# EEZ_CF-DIC_r3B4.net
KiCad netlist of a schematic drawn in EAGLE
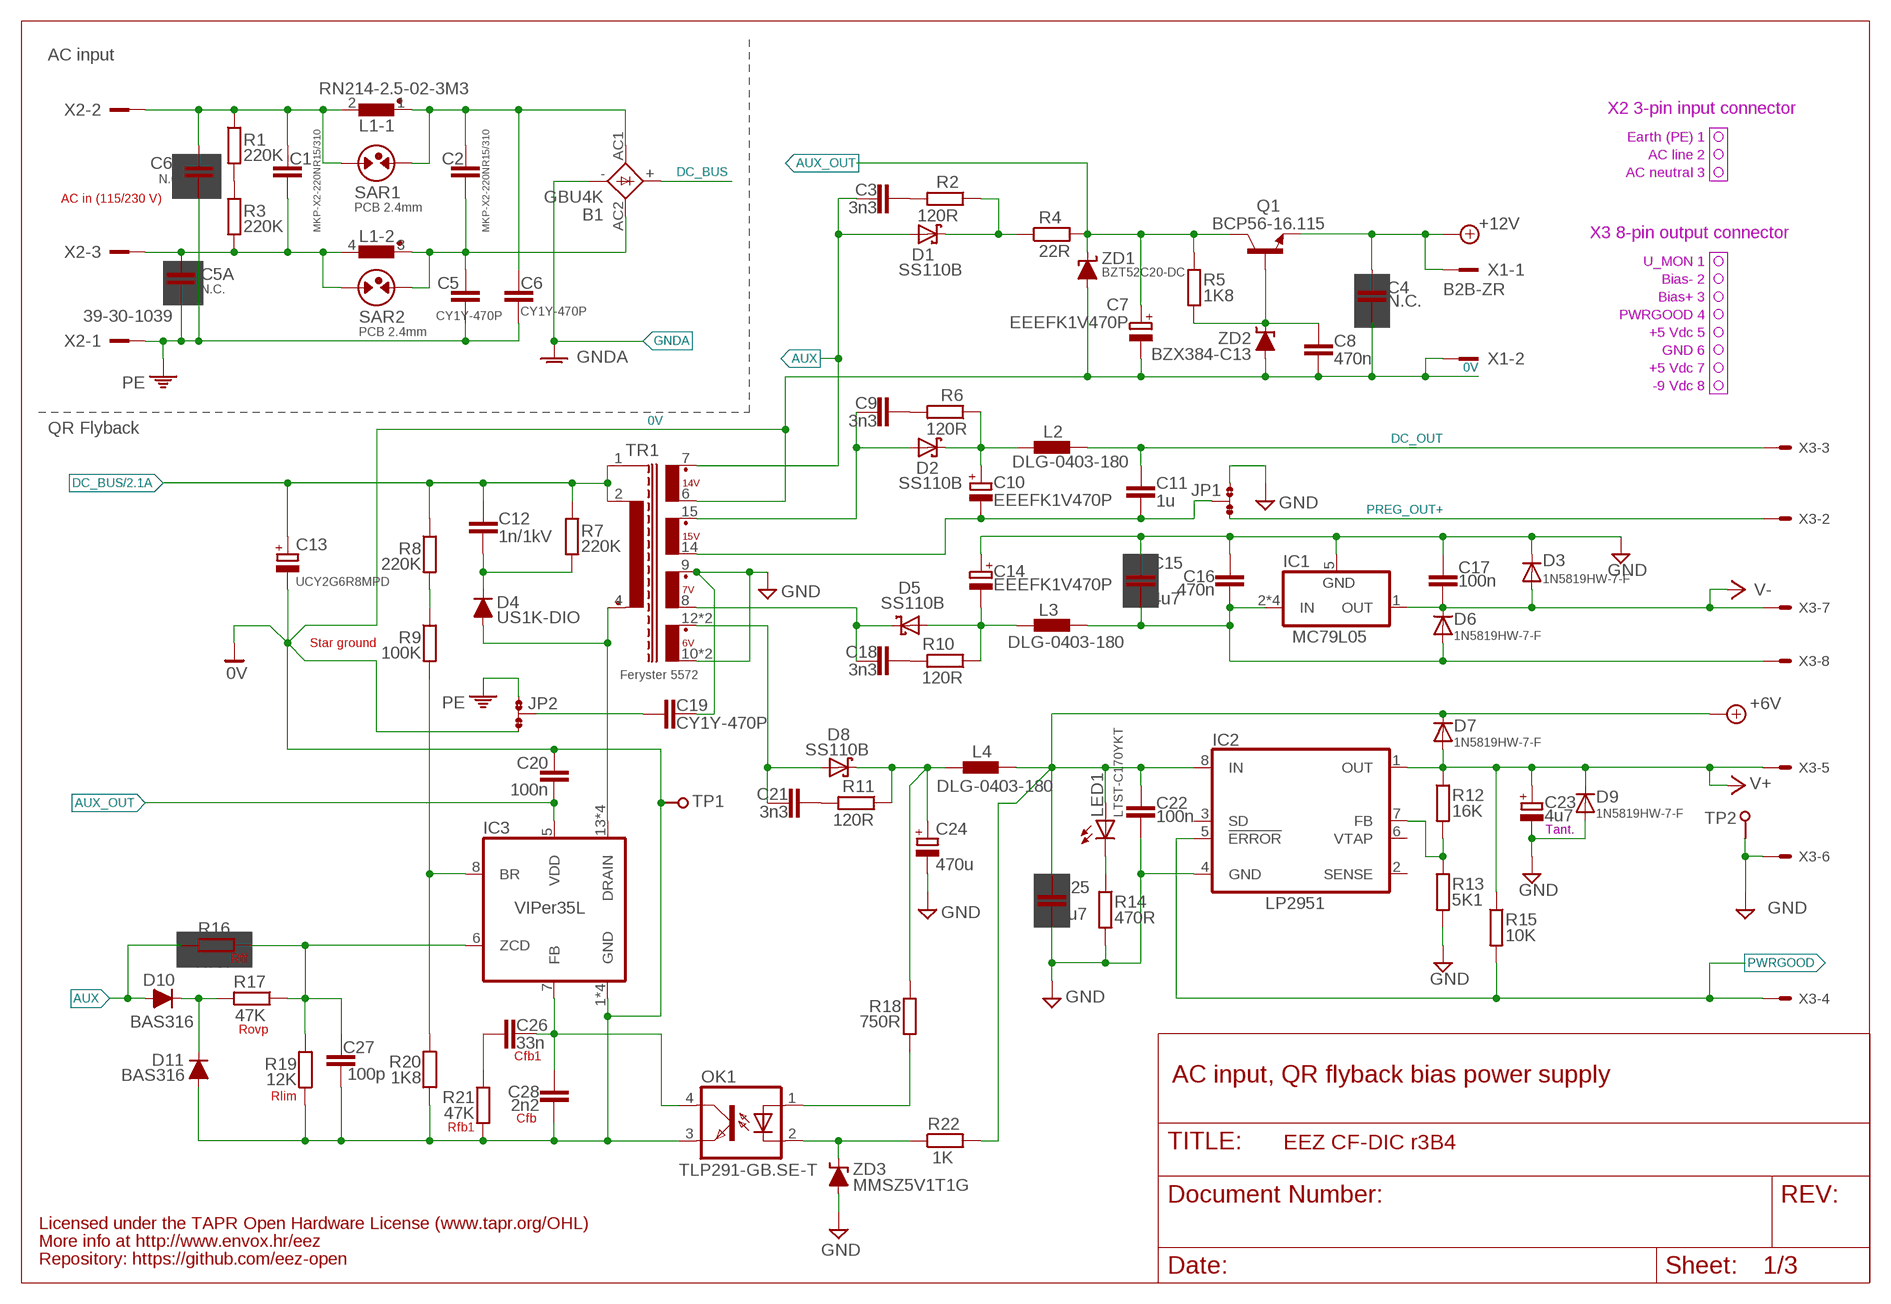
[diagram p0: schematic, sheet 1]
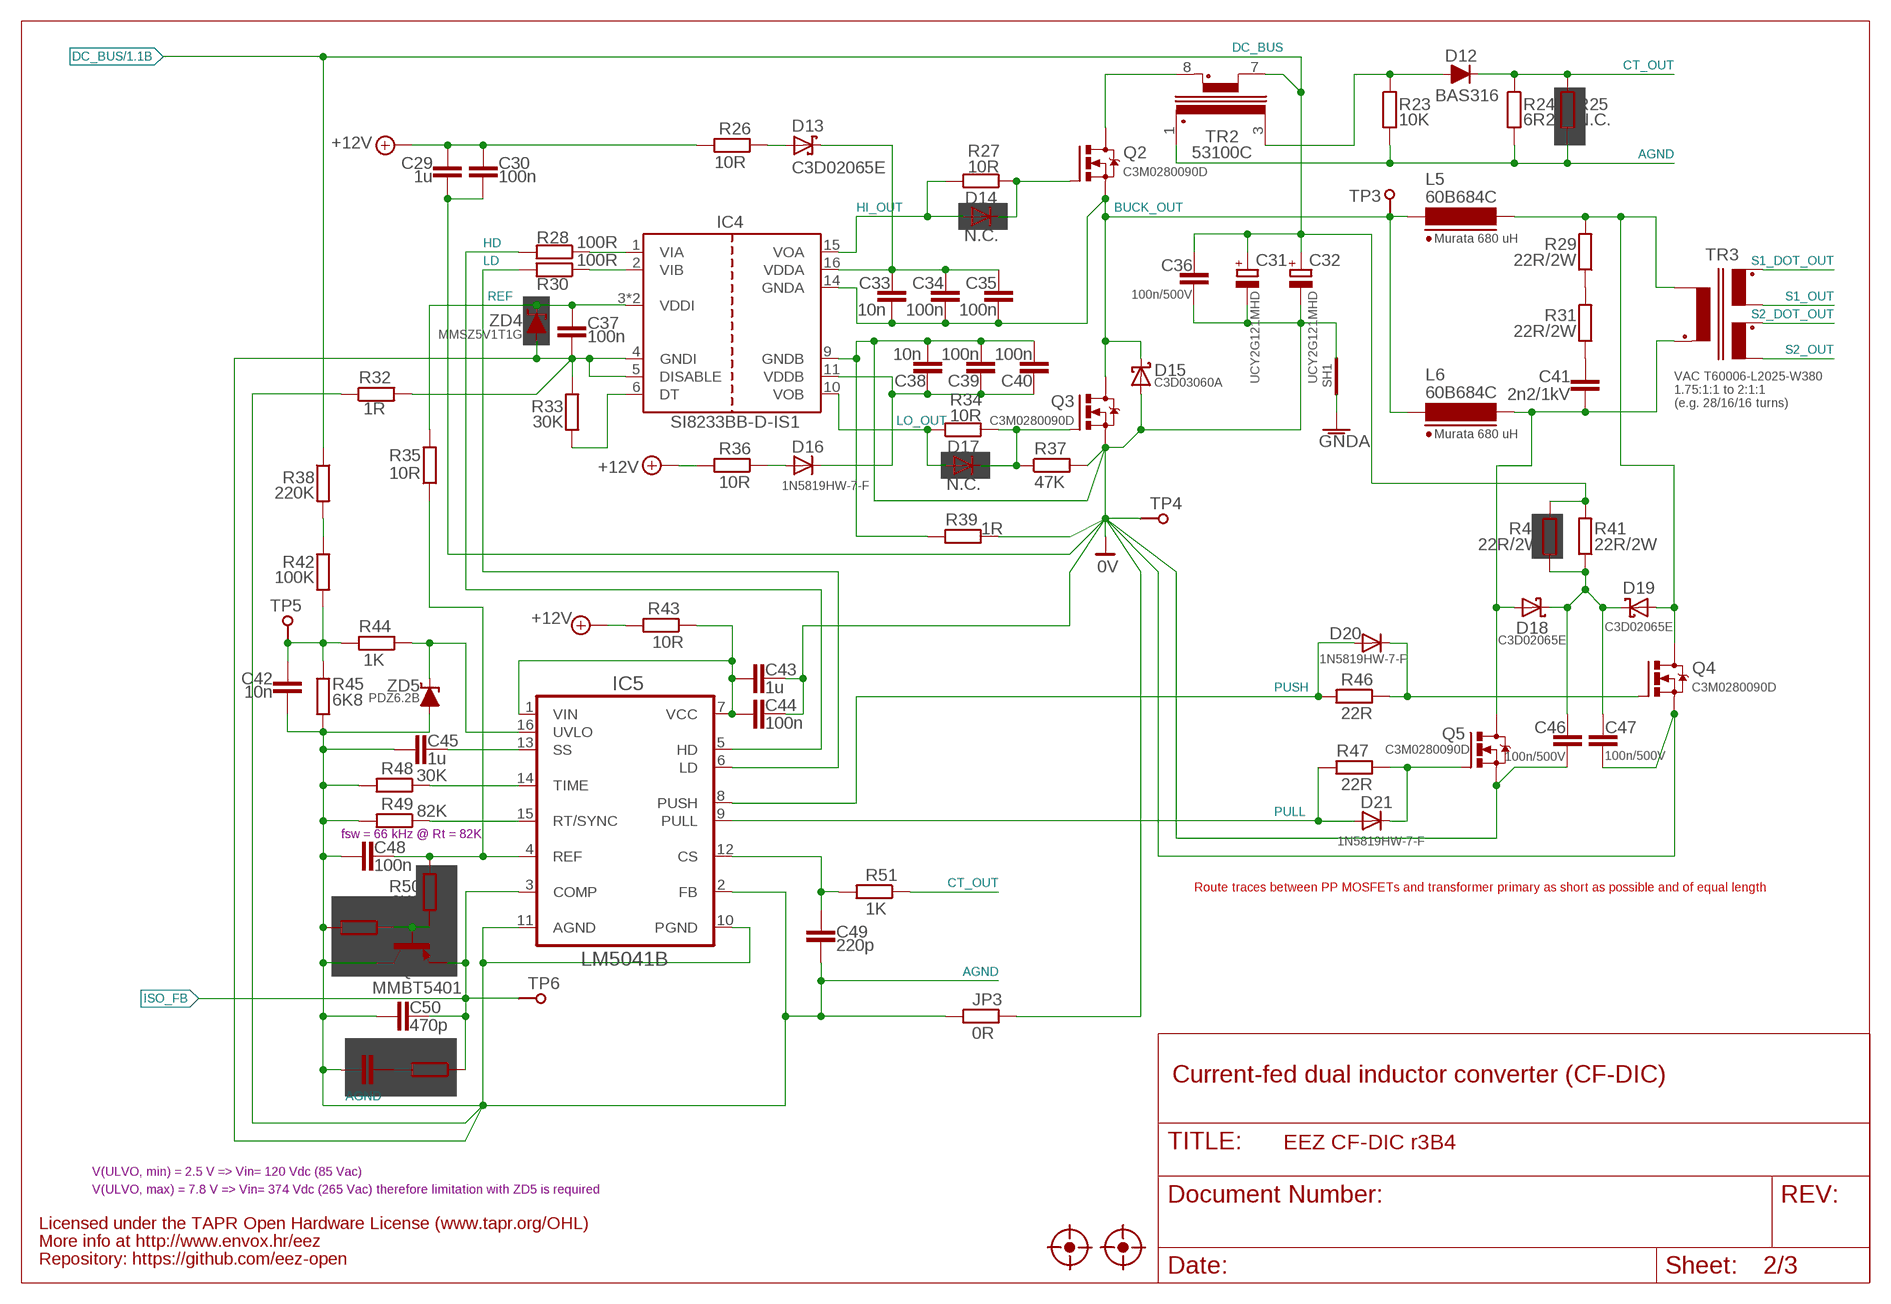
[diagram p1: schematic, sheet 2]
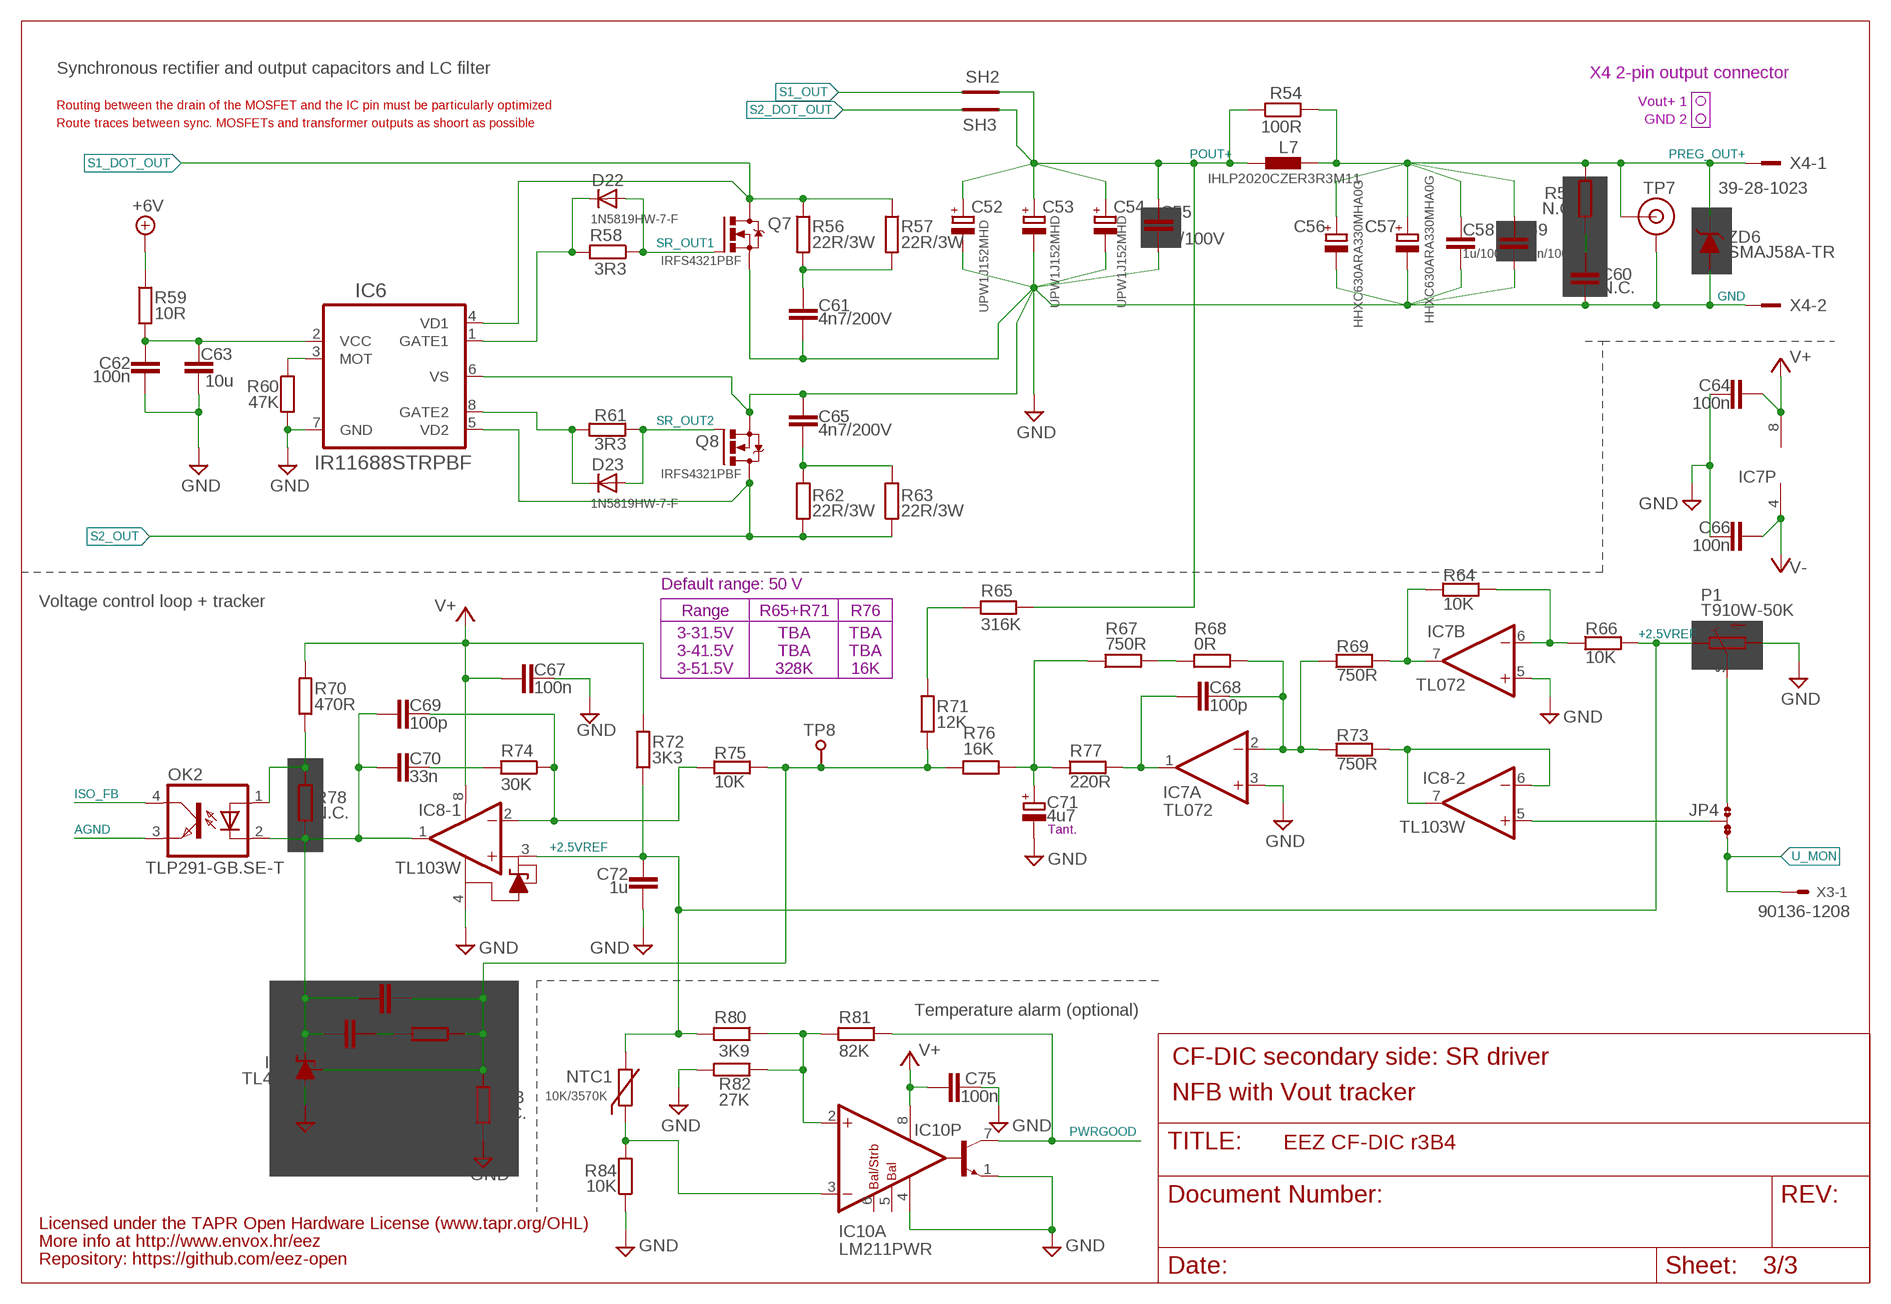
[diagram p2: schematic, sheet 3]

(export (version "E")
  (design (tool "Eeschema 10.0.6"))
  (components
    (comp (ref "B1")
      (value "GBU4K")
      (footprint "eagle-import:GBU4K_CRE")
      (libsource (lib "eagle-import") (part "BRIDGE-CREEPAGE"))
    )
    (comp (ref "C1")
      (value "MKP-X2-220NR15/310")
      (footprint "eagle-import:C150-072X183")
      (libsource (lib "eagle-import") (part "C-EU150-072X183"))
    )
    (comp (ref "C2")
      (value "MKP-X2-220NR15/310")
      (footprint "eagle-import:C150-072X183")
      (libsource (lib "eagle-import") (part "C-EU150-072X183"))
    )
    (comp (ref "C3")
      (value "3n3")
      (footprint "eagle-import:C0805")
      (libsource (lib "eagle-import") (part "C-EUC0805"))
    )
    (comp (ref "C4")
      (value "N.C.")
      (footprint "eagle-import:C0603")
      (libsource (lib "eagle-import") (part "C-EUC0603"))
    )
    (comp (ref "C5")
      (value "CY1Y-470P")
      (footprint "eagle-import:CY075-032X103")
      (libsource (lib "eagle-import") (part "C-EUCY"))
    )
    (comp (ref "C5A")
      (value "N.C.")
      (footprint "eagle-import:CY075-032X103")
      (libsource (lib "eagle-import") (part "C-EUCY"))
    )
    (comp (ref "C6")
      (value "CY1Y-470P")
      (footprint "eagle-import:CY075-032X103")
      (libsource (lib "eagle-import") (part "C-EUCY"))
    )
    (comp (ref "C6A")
      (value "N.C.")
      (footprint "eagle-import:CY075-032X103")
      (libsource (lib "eagle-import") (part "C-EUCY"))
    )
    (comp (ref "C7")
      (value "EEEFK1V470P")
      (footprint "eagle-import:CAPAE660X610N")
      (libsource (lib "eagle-import") (part "ECAPPANASONIC_H"))
    )
    (comp (ref "C8")
      (value "470n")
      (footprint "eagle-import:C0805")
      (libsource (lib "eagle-import") (part "C-EUC0805"))
    )
    (comp (ref "C9")
      (value "3n3")
      (footprint "eagle-import:C0805")
      (libsource (lib "eagle-import") (part "C-EUC0805"))
    )
    (comp (ref "C10")
      (value "EEEFK1V470P")
      (footprint "eagle-import:CAPAE660X610N")
      (libsource (lib "eagle-import") (part "ECAPPANASONIC_H"))
    )
    (comp (ref "C11")
      (value "1u")
      (footprint "eagle-import:C0805")
      (libsource (lib "eagle-import") (part "C-EUC0805"))
    )
    (comp (ref "C12")
      (value "1n/1kV")
      (footprint "eagle-import:C1210")
      (libsource (lib "eagle-import") (part "C-EUC1210"))
    )
    (comp (ref "C13")
      (value "UCY2G6R8MPD")
      (footprint "eagle-import:ECAP5_10.5")
      (libsource (lib "eagle-import") (part "ECAP5G_10.5MM"))
    )
    (comp (ref "C14")
      (value "EEEFK1V470P")
      (footprint "eagle-import:CAPAE660X610N")
      (libsource (lib "eagle-import") (part "ECAPPANASONIC_H"))
    )
    (comp (ref "C15")
      (value "4u7")
      (footprint "eagle-import:C1206")
      (libsource (lib "eagle-import") (part "C-EUC1206"))
    )
    (comp (ref "C16")
      (value "470n")
      (footprint "eagle-import:C0805")
      (libsource (lib "eagle-import") (part "C-EUC0805"))
    )
    (comp (ref "C17")
      (value "100n")
      (footprint "eagle-import:C0603")
      (libsource (lib "eagle-import") (part "C-EUC0603"))
    )
    (comp (ref "C18")
      (value "3n3")
      (footprint "eagle-import:C0805")
      (libsource (lib "eagle-import") (part "C-EUC0805"))
    )
    (comp (ref "C19")
      (value "CY1Y-470P")
      (footprint "eagle-import:CY075-032X103")
      (libsource (lib "eagle-import") (part "C-EUCY"))
    )
    (comp (ref "C20")
      (value "100n")
      (footprint "eagle-import:C0603")
      (libsource (lib "eagle-import") (part "C-EUC0603"))
    )
    (comp (ref "C21")
      (value "3n3")
      (footprint "eagle-import:C0805")
      (libsource (lib "eagle-import") (part "C-EUC0805"))
    )
    (comp (ref "C22")
      (value "100n")
      (footprint "eagle-import:C0603")
      (libsource (lib "eagle-import") (part "C-EUC0603"))
    )
    (comp (ref "C23")
      (value "4u7")
      (footprint "eagle-import:EC1206")
      (libsource (lib "eagle-import") (part "ECAP1206"))
    )
    (comp (ref "C24")
      (value "470u")
      (footprint "eagle-import:ECAP5_10.5")
      (libsource (lib "eagle-import") (part "ECAP5G_10.5MM"))
    )
    (comp (ref "C25")
      (value "4u7")
      (footprint "eagle-import:C1206")
      (libsource (lib "eagle-import") (part "C-EUC1206"))
    )
    (comp (ref "C26")
      (value "33n")
      (footprint "eagle-import:C0805")
      (libsource (lib "eagle-import") (part "C-EUC0805"))
    )
    (comp (ref "C27")
      (value "100p")
      (footprint "eagle-import:C0805")
      (libsource (lib "eagle-import") (part "C-EUC0805"))
    )
    (comp (ref "C28")
      (value "2n2")
      (footprint "eagle-import:C0805")
      (libsource (lib "eagle-import") (part "C-EUC0805"))
    )
    (comp (ref "D1")
      (value "SS110B")
      (footprint "eagle-import:SMB")
      (libsource (lib "eagle-import") (part "SCHOTTKYSMB"))
    )
    (comp (ref "D2")
      (value "SS110B")
      (footprint "eagle-import:SMB")
      (libsource (lib "eagle-import") (part "SCHOTTKYSMB"))
    )
    (comp (ref "D3")
      (value "1N5819HW-7-F")
      (footprint "eagle-import:SOD323-W")
      (libsource (lib "eagle-import") (part "DIODE-SOD323-W"))
    )
    (comp (ref "D4")
      (value "US1K-DIO")
      (footprint "eagle-import:DO214AA")
      (libsource (lib "eagle-import") (part "DIODEDO214AA"))
    )
    (comp (ref "D5")
      (value "SS110B")
      (footprint "eagle-import:SMB")
      (libsource (lib "eagle-import") (part "SCHOTTKYSMB"))
    )
    (comp (ref "D6")
      (value "1N5819HW-7-F")
      (footprint "eagle-import:SOD323-W")
      (libsource (lib "eagle-import") (part "DIODE-SOD323-W"))
    )
    (comp (ref "D7")
      (value "1N5819HW-7-F")
      (footprint "eagle-import:SOD323-W")
      (libsource (lib "eagle-import") (part "DIODE-SOD323-W"))
    )
    (comp (ref "D8")
      (value "SS110B")
      (footprint "eagle-import:SMB")
      (libsource (lib "eagle-import") (part "SCHOTTKYSMB"))
    )
    (comp (ref "D9")
      (value "1N5819HW-7-F")
      (footprint "eagle-import:SOD323-W")
      (libsource (lib "eagle-import") (part "DIODE-SOD323-W"))
    )
    (comp (ref "D10")
      (value "BAS316")
      (footprint "eagle-import:SOD323-R")
      (libsource (lib "eagle-import") (part "DIODESOD323R"))
    )
    (comp (ref "D11")
      (value "BAS316")
      (footprint "eagle-import:SOD323-R")
      (libsource (lib "eagle-import") (part "DIODESOD323R"))
    )
    (comp (ref "IC1")
      (value "MC79L05")
      (footprint "eagle-import:SOIC127P600X173-8N")
      (libsource (lib "eagle-import") (part "MC79LXXSOIC"))
    )
    (comp (ref "IC2")
      (value "LP2951")
      (footprint "eagle-import:SOIC127P600X175-8N")
      (libsource (lib "eagle-import") (part "LP2951SO8"))
    )
    (comp (ref "IC3")
      (value "VIPer35L")
      (footprint "eagle-import:SOIC-16")
      (libsource (lib "eagle-import") (part "VIPER35"))
    )
    (comp (ref "JP1")
      (value "JP3-CUT")
      (footprint "eagle-import:JP3-CUT")
      (libsource (lib "eagle-import") (part "JP3-CUT"))
    )
    (comp (ref "JP2")
      (value "JP3-CUT")
      (footprint "eagle-import:JP3-CUT")
      (libsource (lib "eagle-import") (part "JP3-CUT"))
    )
    (comp (ref "L1")
      (value "RN214-2.5-02-3M3")
      (footprint "eagle-import:RN214")
      (fields (field (name "FARNELL") "1191518"))
      (libsource (lib "eagle-import") (part "EEZ_inductors_and_transformers_RN214"))
    )
    (comp (ref "L2")
      (value "DLG-0403-180")
      (footprint "eagle-import:DE0403")
      (libsource (lib "eagle-import") (part "EEZ_inductors_and_transformers_DE0403"))
    )
    (comp (ref "L3")
      (value "DLG-0403-180")
      (footprint "eagle-import:DE0403")
      (libsource (lib "eagle-import") (part "EEZ_inductors_and_transformers_DE0403"))
    )
    (comp (ref "L4")
      (value "DLG-0403-180")
      (footprint "eagle-import:DE0403")
      (libsource (lib "eagle-import") (part "EEZ_inductors_and_transformers_DE0403"))
    )
    (comp (ref "LED1")
      (value "LTST-C170YKT")
      (footprint "eagle-import:LED_0805")
      (libsource (lib "eagle-import") (part "LED0805"))
    )
    (comp (ref "OK1")
      (value "TLP291-GB.SE-T")
      (footprint "eagle-import:SO4")
      (libsource (lib "eagle-import") (part "TLP291"))
    )
    (comp (ref "Q1")
      (value "BCP56-16.115")
      (footprint "eagle-import:SOT230P700X180-4N")
      (libsource (lib "eagle-import") (part "BCP56"))
    )
    (comp (ref "R1")
      (value "220K")
      (footprint "eagle-import:R1206")
      (libsource (lib "eagle-import") (part "R-EU_R1206"))
    )
    (comp (ref "R2")
      (value "120R")
      (footprint "eagle-import:R0805")
      (libsource (lib "eagle-import") (part "R-EU_R0805"))
    )
    (comp (ref "R3")
      (value "220K")
      (footprint "eagle-import:R1206")
      (libsource (lib "eagle-import") (part "R-EU_R1206"))
    )
    (comp (ref "R4")
      (value "22R")
      (footprint "eagle-import:R0805")
      (libsource (lib "eagle-import") (part "R-EU_R0805"))
    )
    (comp (ref "R5")
      (value "1K8")
      (footprint "eagle-import:R0805")
      (libsource (lib "eagle-import") (part "R-EU_R0805"))
    )
    (comp (ref "R6")
      (value "120R")
      (footprint "eagle-import:R0805")
      (libsource (lib "eagle-import") (part "R-EU_R0805"))
    )
    (comp (ref "R7")
      (value "220K")
      (footprint "eagle-import:R1206")
      (libsource (lib "eagle-import") (part "R-EU_R1206"))
    )
    (comp (ref "R8")
      (value "220K")
      (footprint "eagle-import:R1206")
      (libsource (lib "eagle-import") (part "R-EU_R1206"))
    )
    (comp (ref "R9")
      (value "100K")
      (footprint "eagle-import:R0805")
      (libsource (lib "eagle-import") (part "R-EU_R0805"))
    )
    (comp (ref "R10")
      (value "120R")
      (footprint "eagle-import:R0805")
      (libsource (lib "eagle-import") (part "R-EU_R0805"))
    )
    (comp (ref "R11")
      (value "120R")
      (footprint "eagle-import:R0805")
      (libsource (lib "eagle-import") (part "R-EU_R0805"))
    )
    (comp (ref "R12")
      (value "16K")
      (footprint "eagle-import:R0805")
      (libsource (lib "eagle-import") (part "R-EU_R0805"))
    )
    (comp (ref "R13")
      (value "5K1")
      (footprint "eagle-import:R0805")
      (libsource (lib "eagle-import") (part "R-EU_R0805"))
    )
    (comp (ref "R14")
      (value "470R")
      (footprint "eagle-import:R0805")
      (libsource (lib "eagle-import") (part "R-EU_R0805"))
    )
    (comp (ref "R15")
      (value "10K")
      (footprint "eagle-import:R0805")
      (libsource (lib "eagle-import") (part "R-EU_R0805"))
    )
    (comp (ref "R16")
      (value "N.C.")
      (footprint "eagle-import:R0805")
      (libsource (lib "eagle-import") (part "R-EU_R0805"))
    )
    (comp (ref "R17")
      (value "47K")
      (footprint "eagle-import:R0805")
      (libsource (lib "eagle-import") (part "R-EU_R0805"))
    )
    (comp (ref "R18")
      (value "750R")
      (footprint "eagle-import:R0805")
      (libsource (lib "eagle-import") (part "R-EU_R0805"))
    )
    (comp (ref "R19")
      (value "12K")
      (footprint "eagle-import:R0805")
      (libsource (lib "eagle-import") (part "R-EU_R0805"))
    )
    (comp (ref "R20")
      (value "1K8")
      (footprint "eagle-import:R0805")
      (libsource (lib "eagle-import") (part "R-EU_R0805"))
    )
    (comp (ref "R21")
      (value "47K")
      (footprint "eagle-import:R0805")
      (libsource (lib "eagle-import") (part "R-EU_R0805"))
    )
    (comp (ref "R22")
      (value "1K")
      (footprint "eagle-import:R0805")
      (libsource (lib "eagle-import") (part "R-EU_R0805"))
    )
    (comp (ref "SAR1")
      (value "PCB 2.4mm")
      (footprint "eagle-import:PCB-SAR_2.4MM")
      (libsource (lib "eagle-import") (part "SARPCB-2.4MM"))
    )
    (comp (ref "SAR2")
      (value "PCB 2.4mm")
      (footprint "eagle-import:PCB-SAR_2.4MM")
      (libsource (lib "eagle-import") (part "SARPCB-2.4MM"))
    )
    (comp (ref "TP1")
      (value "PCB_TEST_TABSHIELD")
      (footprint "eagle-import:PCB_SHIELD_TAB")
      (libsource (lib "eagle-import") (part "PCB_TEST_TABSHIELD"))
    )
    (comp (ref "TP2")
      (value "PCB_TEST_TABSHIELD")
      (footprint "eagle-import:PCB_SHIELD_TAB")
      (libsource (lib "eagle-import") (part "PCB_TEST_TABSHIELD"))
    )
    (comp (ref "TR1")
      (value "Feryster 5572")
      (footprint "eagle-import:FERYSTER_5572")
      (libsource (lib "eagle-import") (part "EEZ_inductors_and_transformers_FERYSTER_5572"))
    )
    (comp (ref "X1")
      (value "B2B-ZR")
      (footprint "eagle-import:B2B-ZR")
      (libsource (lib "eagle-import") (part "B2B-ZR"))
    )
    (comp (ref "X2")
      (value "39-30-1039")
      (footprint "eagle-import:MINIFIT_39301039_CRE")
      (libsource (lib "eagle-import") (part "MINIFIT_39301039-CREEPAGE"))
    )
    (comp (ref "X3")
      (value "90136-1208")
      (footprint "eagle-import:70543-08")
      (libsource (lib "eagle-import") (part "C-GRID-08-70543"))
    )
    (comp (ref "ZD1")
      (value "BZT52C20-DC")
      (footprint "eagle-import:SOD123FL")
      (libsource (lib "eagle-import") (part "ZENER-DIODESOD123FL"))
    )
    (comp (ref "ZD2")
      (value "BZX384-C13")
      (footprint "eagle-import:SOD323-W")
      (libsource (lib "eagle-import") (part "ZENER-DIODESOD323"))
    )
    (comp (ref "ZD3")
      (value "MMSZ5V1T1G")
      (footprint "eagle-import:SOD323-W")
      (libsource (lib "eagle-import") (part "ZENER-DIODESOD323"))
    )
    (comp (ref "C29")
      (value "1u")
      (footprint "eagle-import:C0805")
      (libsource (lib "eagle-import") (part "C-EUC0805"))
    )
    (comp (ref "C30")
      (value "100n")
      (footprint "eagle-import:C0603")
      (libsource (lib "eagle-import") (part "C-EUC0603"))
    )
    (comp (ref "C31")
      (value "UCY2G121MHD")
      (footprint "eagle-import:ECAP7.5_18")
      (libsource (lib "eagle-import") (part "ECAP7.5G_18MM"))
    )
    (comp (ref "C32")
      (value "UCY2G121MHD")
      (footprint "eagle-import:ECAP7.5_18")
      (libsource (lib "eagle-import") (part "ECAP7.5G_18MM"))
    )
    (comp (ref "C33")
      (value "10n")
      (footprint "eagle-import:C0603")
      (libsource (lib "eagle-import") (part "C-EUC0603"))
    )
    (comp (ref "C34")
      (value "100n")
      (footprint "eagle-import:C0603")
      (libsource (lib "eagle-import") (part "C-EUC0603"))
    )
    (comp (ref "C35")
      (value "100n")
      (footprint "eagle-import:C0603")
      (libsource (lib "eagle-import") (part "C-EUC0603"))
    )
    (comp (ref "C36")
      (value "100n/500V")
      (footprint "eagle-import:C1812")
      (libsource (lib "eagle-import") (part "C-EUC1812"))
    )
    (comp (ref "C37")
      (value "100n")
      (footprint "eagle-import:C0603")
      (libsource (lib "eagle-import") (part "C-EUC0603"))
    )
    (comp (ref "C38")
      (value "10n")
      (footprint "eagle-import:C0603")
      (libsource (lib "eagle-import") (part "C-EUC0603"))
    )
    (comp (ref "C39")
      (value "100n")
      (footprint "eagle-import:C0603")
      (libsource (lib "eagle-import") (part "C-EUC0603"))
    )
    (comp (ref "C40")
      (value "100n")
      (footprint "eagle-import:C0603")
      (libsource (lib "eagle-import") (part "C-EUC0603"))
    )
    (comp (ref "C41")
      (value "2n2/1kV")
      (footprint "eagle-import:C1210")
      (libsource (lib "eagle-import") (part "C-EUC1210"))
    )
    (comp (ref "C42")
      (value "10n")
      (footprint "eagle-import:C0603")
      (libsource (lib "eagle-import") (part "C-EUC0603"))
    )
    (comp (ref "C43")
      (value "1u")
      (footprint "eagle-import:C0805")
      (libsource (lib "eagle-import") (part "C-EUC0805"))
    )
    (comp (ref "C44")
      (value "100n")
      (footprint "eagle-import:C0603")
      (libsource (lib "eagle-import") (part "C-EUC0603"))
    )
    (comp (ref "C45")
      (value "1u")
      (footprint "eagle-import:C0805")
      (libsource (lib "eagle-import") (part "C-EUC0805"))
    )
    (comp (ref "C46")
      (value "100n/500V")
      (footprint "eagle-import:C1812")
      (libsource (lib "eagle-import") (part "C-EUC1812"))
    )
    (comp (ref "C47")
      (value "100n/500V")
      (footprint "eagle-import:C1812")
      (libsource (lib "eagle-import") (part "C-EUC1812"))
    )
    (comp (ref "C48")
      (value "100n")
      (footprint "eagle-import:C0603")
      (libsource (lib "eagle-import") (part "C-EUC0603"))
    )
    (comp (ref "C49")
      (value "220p")
      (footprint "eagle-import:C0805")
      (libsource (lib "eagle-import") (part "C-EUC0805"))
    )
    (comp (ref "C50")
      (value "470p")
      (footprint "eagle-import:C0805")
      (libsource (lib "eagle-import") (part "C-EUC0805"))
    )
    (comp (ref "C51")
      (value "N.C.")
      (footprint "eagle-import:C0805")
      (libsource (lib "eagle-import") (part "C-EUC0805"))
    )
    (comp (ref "D12")
      (value "BAS316")
      (footprint "eagle-import:SOD323-R")
      (libsource (lib "eagle-import") (part "DIODESOD323R"))
    )
    (comp (ref "D13")
      (value "C3D02065E")
      (footprint "eagle-import:TO252")
      (libsource (lib "eagle-import") (part "SCHOTTKY-2"))
    )
    (comp (ref "D14")
      (value "N.C.")
      (footprint "eagle-import:SOD323-W")
      (libsource (lib "eagle-import") (part "DIODE-SOD323-W"))
    )
    (comp (ref "D15")
      (value "C3D03060A")
      (footprint "eagle-import:TO220-2")
      (libsource (lib "eagle-import") (part "SCHOTTKY-TO220"))
    )
    (comp (ref "D16")
      (value "1N5819HW-7-F")
      (footprint "eagle-import:SOD323-W")
      (libsource (lib "eagle-import") (part "DIODE-SOD323-W"))
    )
    (comp (ref "D17")
      (value "N.C.")
      (footprint "eagle-import:SOD323-W")
      (libsource (lib "eagle-import") (part "DIODE-SOD323-W"))
    )
    (comp (ref "D18")
      (value "C3D02065E")
      (footprint "eagle-import:TO252")
      (libsource (lib "eagle-import") (part "SCHOTTKY-2"))
    )
    (comp (ref "D19")
      (value "C3D02065E")
      (footprint "eagle-import:TO252")
      (libsource (lib "eagle-import") (part "SCHOTTKY-2"))
    )
    (comp (ref "D20")
      (value "1N5819HW-7-F")
      (footprint "eagle-import:SOD323-W")
      (libsource (lib "eagle-import") (part "DIODE-SOD323-W"))
    )
    (comp (ref "D21")
      (value "1N5819HW-7-F")
      (footprint "eagle-import:SOD323-W")
      (libsource (lib "eagle-import") (part "DIODE-SOD323-W"))
    )
    (comp (ref "FM1")
      (value "FIDUCIAL_2")
      (footprint "eagle-import:FIDUCIAL_DUAL")
      (libsource (lib "eagle-import") (part "FIDUCIAL_2"))
    )
    (comp (ref "FM2")
      (value "FIDUCIAL_2")
      (footprint "eagle-import:FIDUCIAL_DUAL")
      (libsource (lib "eagle-import") (part "FIDUCIAL_2"))
    )
    (comp (ref "IC4")
      (value "SI8233BB-D-IS1")
      (footprint "eagle-import:SOIC-16")
      (libsource (lib "eagle-import") (part "SI8233"))
    )
    (comp (ref "IC5")
      (value "LM5041B")
      (footprint "eagle-import:MTC16")
      (fields (field (name "MANUFACTURER_PART_NUMBER") "lm5041mtcnopb"))
      (libsource (lib "eagle-import") (part "LM5041"))
    )
    (comp (ref "JP3")
      (value "0R")
      (footprint "eagle-import:R0805")
      (libsource (lib "eagle-import") (part "R-EU_R0805"))
    )
    (comp (ref "L5")
      (value "60B684C")
      (footprint "eagle-import:MURATA_6000B")
      (libsource (lib "eagle-import") (part "EEZ_inductors_and_transformers_MURATA_6000B"))
    )
    (comp (ref "L6")
      (value "60B684C")
      (footprint "eagle-import:MURATA_6000B")
      (libsource (lib "eagle-import") (part "EEZ_inductors_and_transformers_MURATA_6000B"))
    )
    (comp (ref "Q2")
      (value "C3M0280090D")
      (footprint "eagle-import:TO247BV")
      (libsource (lib "eagle-import") (part "IRFP240"))
    )
    (comp (ref "Q3")
      (value "C3M0280090D")
      (footprint "eagle-import:TO247BV")
      (libsource (lib "eagle-import") (part "IRFP240"))
    )
    (comp (ref "Q4")
      (value "C3M0280090D")
      (footprint "eagle-import:TO247BV")
      (libsource (lib "eagle-import") (part "IRFP240"))
    )
    (comp (ref "Q5")
      (value "C3M0280090D")
      (footprint "eagle-import:TO247BV")
      (libsource (lib "eagle-import") (part "IRFP240"))
    )
    (comp (ref "Q6")
      (value "MMBT5401")
      (footprint "eagle-import:SOT23-BEC")
      (libsource (lib "eagle-import") (part "-PNP-SOT23-BECBC857B"))
    )
    (comp (ref "R23")
      (value "10K")
      (footprint "eagle-import:R0805")
      (libsource (lib "eagle-import") (part "R-EU_R0805"))
    )
    (comp (ref "R24")
      (value "6R2")
      (footprint "eagle-import:R0805")
      (libsource (lib "eagle-import") (part "R-EU_R0805"))
    )
    (comp (ref "R25")
      (value "N.C.")
      (footprint "eagle-import:R0805")
      (libsource (lib "eagle-import") (part "R-EU_R0805"))
    )
    (comp (ref "R26")
      (value "10R")
      (footprint "eagle-import:R0805")
      (libsource (lib "eagle-import") (part "R-EU_R0805"))
    )
    (comp (ref "R27")
      (value "10R")
      (footprint "eagle-import:R0805")
      (libsource (lib "eagle-import") (part "R-EU_R0805"))
    )
    (comp (ref "R28")
      (value "100R")
      (footprint "eagle-import:R0805")
      (libsource (lib "eagle-import") (part "R-EU_R0805"))
    )
    (comp (ref "R29")
      (value "22R/2W")
      (footprint "eagle-import:R2512")
      (libsource (lib "eagle-import") (part "R-EU_R2512"))
    )
    (comp (ref "R30")
      (value "100R")
      (footprint "eagle-import:R0805")
      (libsource (lib "eagle-import") (part "R-EU_R0805"))
    )
    (comp (ref "R31")
      (value "22R/2W")
      (footprint "eagle-import:R2512")
      (libsource (lib "eagle-import") (part "R-EU_R2512"))
    )
    (comp (ref "R32")
      (value "1R")
      (footprint "eagle-import:R0805")
      (libsource (lib "eagle-import") (part "R-EU_R0805"))
    )
    (comp (ref "R33")
      (value "30K")
      (footprint "eagle-import:R0805")
      (libsource (lib "eagle-import") (part "R-EU_R0805"))
    )
    (comp (ref "R34")
      (value "10R")
      (footprint "eagle-import:R0805")
      (libsource (lib "eagle-import") (part "R-EU_R0805"))
    )
    (comp (ref "R35")
      (value "10R")
      (footprint "eagle-import:R0805")
      (libsource (lib "eagle-import") (part "R-EU_R0805"))
    )
    (comp (ref "R36")
      (value "10R")
      (footprint "eagle-import:R0805")
      (libsource (lib "eagle-import") (part "R-EU_R0805"))
    )
    (comp (ref "R37")
      (value "47K")
      (footprint "eagle-import:R0805")
      (libsource (lib "eagle-import") (part "R-EU_R0805"))
    )
    (comp (ref "R38")
      (value "220K")
      (footprint "eagle-import:R1206")
      (libsource (lib "eagle-import") (part "R-EU_R1206"))
    )
    (comp (ref "R39")
      (value "1R")
      (footprint "eagle-import:R0805")
      (libsource (lib "eagle-import") (part "R-EU_R0805"))
    )
    (comp (ref "R40")
      (value "22R/2W")
      (footprint "eagle-import:R2512")
      (libsource (lib "eagle-import") (part "R-EU_R2512"))
    )
    (comp (ref "R41")
      (value "22R/2W")
      (footprint "eagle-import:R2512")
      (libsource (lib "eagle-import") (part "R-EU_R2512"))
    )
    (comp (ref "R42")
      (value "100K")
      (footprint "eagle-import:R0805")
      (libsource (lib "eagle-import") (part "R-EU_R0805"))
    )
    (comp (ref "R43")
      (value "10R")
      (footprint "eagle-import:R0805")
      (libsource (lib "eagle-import") (part "R-EU_R0805"))
    )
    (comp (ref "R44")
      (value "1K")
      (footprint "eagle-import:R0805")
      (libsource (lib "eagle-import") (part "R-EU_R0805"))
    )
    (comp (ref "R45")
      (value "6K8")
      (footprint "eagle-import:R0805")
      (libsource (lib "eagle-import") (part "R-EU_R0805"))
    )
    (comp (ref "R46")
      (value "22R")
      (footprint "eagle-import:R0805")
      (libsource (lib "eagle-import") (part "R-EU_R0805"))
    )
    (comp (ref "R47")
      (value "22R")
      (footprint "eagle-import:R0805")
      (libsource (lib "eagle-import") (part "R-EU_R0805"))
    )
    (comp (ref "R48")
      (value "30K")
      (footprint "eagle-import:R0805")
      (libsource (lib "eagle-import") (part "R-EU_R0805"))
    )
    (comp (ref "R49")
      (value "82K")
      (footprint "eagle-import:R0805")
      (libsource (lib "eagle-import") (part "R-EU_R0805"))
    )
    (comp (ref "R50")
      (value "6K8")
      (footprint "eagle-import:R0805")
      (libsource (lib "eagle-import") (part "R-EU_R0805"))
    )
    (comp (ref "R51")
      (value "1K")
      (footprint "eagle-import:R0805")
      (libsource (lib "eagle-import") (part "R-EU_R0805"))
    )
    (comp (ref "R52")
      (value "6K8")
      (footprint "eagle-import:R0805")
      (libsource (lib "eagle-import") (part "R-EU_R0805"))
    )
    (comp (ref "R53")
      (value "N.C.")
      (footprint "eagle-import:R0805")
      (libsource (lib "eagle-import") (part "R-EU_R0805"))
    )
    (comp (ref "SH1")
      (value "SHORTNOHOLE")
      (footprint "eagle-import:SHORT_NOHOLE")
      (libsource (lib "eagle-import") (part "SHORTNOHOLE"))
    )
    (comp (ref "TP3")
      (value "PCB_TEST_TABSHIELD")
      (footprint "eagle-import:PCB_SHIELD_TAB")
      (libsource (lib "eagle-import") (part "PCB_TEST_TABSHIELD"))
    )
    (comp (ref "TP4")
      (value "PCB_TEST_TABSHIELD")
      (footprint "eagle-import:PCB_SHIELD_TAB")
      (libsource (lib "eagle-import") (part "PCB_TEST_TABSHIELD"))
    )
    (comp (ref "TP5")
      (value "PCB_TEST_TABSHIELD")
      (footprint "eagle-import:PCB_SHIELD_TAB")
      (libsource (lib "eagle-import") (part "PCB_TEST_TABSHIELD"))
    )
    (comp (ref "TP6")
      (value "PCB_TEST_TABSHIELD")
      (footprint "eagle-import:PCB_SHIELD_TAB")
      (libsource (lib "eagle-import") (part "PCB_TEST_TABSHIELD"))
    )
    (comp (ref "TR2")
      (value "53100C")
      (footprint "eagle-import:MURATA_5300")
      (libsource (lib "eagle-import") (part "MURATA_5300"))
    )
    (comp (ref "TR3")
      (value "VAC T60006-L2025-W380")
      (footprint "eagle-import:VAC_DUAL_SEC")
      (libsource (lib "eagle-import") (part "PCB_TRAFO_FLYBACK2-VAC"))
    )
    (comp (ref "ZD4")
      (value "MMSZ5V1T1G")
      (footprint "eagle-import:SOD323-W")
      (libsource (lib "eagle-import") (part "ZENER-DIODESOD323"))
    )
    (comp (ref "ZD5")
      (value "PDZ6.2B")
      (footprint "eagle-import:SOD323-W")
      (libsource (lib "eagle-import") (part "ZENER-DIODESOD323"))
    )
    (comp (ref "C52")
      (value "UPW1J152MHD")
      (footprint "eagle-import:ECAP7.5_18")
      (libsource (lib "eagle-import") (part "ECAP7.5G_18MM"))
    )
    (comp (ref "C53")
      (value "UPW1J152MHD")
      (footprint "eagle-import:ECAP7.5_18")
      (libsource (lib "eagle-import") (part "ECAP7.5G_18MM"))
    )
    (comp (ref "C54")
      (value "UPW1J152MHD")
      (footprint "eagle-import:ECAP7.5_18")
      (libsource (lib "eagle-import") (part "ECAP7.5G_18MM"))
    )
    (comp (ref "C55")
      (value "1u/100V")
      (footprint "eagle-import:C1206")
      (libsource (lib "eagle-import") (part "C-EUC1206"))
    )
    (comp (ref "C56")
      (value "HHXC630ARA330MHA0G ")
      (footprint "eagle-import:CAPAE830X1050N")
      (fields
        (field (name "MPN") "EEE-FK1J470P")
        (field (name "TOLERANCE") "±20 %")
        (field (name "MPN_1") "EEE-FK1J470P")
        (field (name "OC_FARNELL") "9696032  ")
        (field (name "OC_NEWARK") "96K9403")
        (field (name "PACKAGE") "CASE-F")
        (field (name "SUPPLIER") "PANASONIC")
        (field (name "TOLERANCE_1") "±20 %")
        (field (name "VOLTAGERATING") "63 V")
      )
      (libsource (lib "eagle-import") (part "EEE--CASE-FFK1J470P"))
    )
    (comp (ref "C57")
      (value "HHXC630ARA330MHA0G")
      (footprint "eagle-import:CAPAE830X1050N")
      (fields (field (name "MPN") "EEE-FK1J470P") (field (name "TOLERANCE") "±20 %"))
      (libsource (lib "eagle-import") (part "EEE--CASE-FFK1J470P"))
    )
    (comp (ref "C58")
      (value "1u/100V")
      (footprint "eagle-import:C1206")
      (libsource (lib "eagle-import") (part "C-EUC1206"))
    )
    (comp (ref "C59")
      (value "100n/100V")
      (footprint "eagle-import:C0805")
      (libsource (lib "eagle-import") (part "C-EUC0805"))
    )
    (comp (ref "C60")
      (value "N.C.")
      (footprint "eagle-import:C1206")
      (libsource (lib "eagle-import") (part "C-EUC1206"))
    )
    (comp (ref "C61")
      (value "4n7/200V")
      (footprint "eagle-import:C1206")
      (libsource (lib "eagle-import") (part "C-EUC1206"))
    )
    (comp (ref "C62")
      (value "100n")
      (footprint "eagle-import:C0603")
      (libsource (lib "eagle-import") (part "C-EUC0603"))
    )
    (comp (ref "C63")
      (value "10u")
      (footprint "eagle-import:C1210")
      (libsource (lib "eagle-import") (part "C-EUC1210"))
    )
    (comp (ref "C64")
      (value "100n")
      (footprint "eagle-import:C0603")
      (libsource (lib "eagle-import") (part "C-EUC0603"))
    )
    (comp (ref "C65")
      (value "4n7/200V")
      (footprint "eagle-import:C1206")
      (libsource (lib "eagle-import") (part "C-EUC1206"))
    )
    (comp (ref "C66")
      (value "100n")
      (footprint "eagle-import:C0603")
      (libsource (lib "eagle-import") (part "C-EUC0603"))
    )
    (comp (ref "C67")
      (value "100n")
      (footprint "eagle-import:C0603")
      (libsource (lib "eagle-import") (part "C-EUC0603"))
    )
    (comp (ref "C68")
      (value "100p")
      (footprint "eagle-import:C0805")
      (libsource (lib "eagle-import") (part "C-EUC0805"))
    )
    (comp (ref "C69")
      (value "100p")
      (footprint "eagle-import:C0805")
      (libsource (lib "eagle-import") (part "C-EUC0805"))
    )
    (comp (ref "C70")
      (value "33n")
      (footprint "eagle-import:C0805")
      (libsource (lib "eagle-import") (part "C-EUC0805"))
    )
    (comp (ref "C71")
      (value "4u7")
      (footprint "eagle-import:EC1206")
      (libsource (lib "eagle-import") (part "ECAP1206"))
    )
    (comp (ref "C72")
      (value "1u")
      (footprint "eagle-import:C0805")
      (libsource (lib "eagle-import") (part "C-EUC0805"))
    )
    (comp (ref "C73")
      (value "N.C.")
      (footprint "eagle-import:C0805")
      (libsource (lib "eagle-import") (part "C-EUC0805"))
    )
    (comp (ref "C74")
      (value "N.C.")
      (footprint "eagle-import:C0805")
      (libsource (lib "eagle-import") (part "C-EUC0805"))
    )
    (comp (ref "C75")
      (value "100n")
      (footprint "eagle-import:C0603")
      (libsource (lib "eagle-import") (part "C-EUC0603"))
    )
    (comp (ref "D22")
      (value "1N5819HW-7-F")
      (footprint "eagle-import:SOD323-W")
      (libsource (lib "eagle-import") (part "DIODE-SOD323-W"))
    )
    (comp (ref "D23")
      (value "1N5819HW-7-F")
      (footprint "eagle-import:SOD323-W")
      (libsource (lib "eagle-import") (part "DIODE-SOD323-W"))
    )
    (comp (ref "IC6")
      (value "IR11688STRPBF")
      (footprint "eagle-import:SO8")
      (libsource (lib "eagle-import") (part "IR11688"))
    )
    (comp (ref "IC7")
      (value "TL072")
      (footprint "eagle-import:SOIC127P600X173-8N")
      (libsource (lib "eagle-import") (part "TL072SOIC8"))
    )
    (comp (ref "IC8")
      (value "TL103W")
      (footprint "eagle-import:SOIC127P600X173-8N")
      (libsource (lib "eagle-import") (part "TL103W"))
    )
    (comp (ref "IC9")
      (value "TL431")
      (footprint "eagle-import:SOT103P240X110-3N")
      (libsource (lib "eagle-import") (part "TL431"))
    )
    (comp (ref "IC10")
      (value "LM211PWR")
      (footprint "eagle-import:PW8_TSSOP8")
      (libsource (lib "eagle-import") (part "LM211"))
    )
    (comp (ref "JP4")
      (value "JP3-CUT")
      (footprint "eagle-import:JP3-CUT")
      (libsource (lib "eagle-import") (part "JP3-CUT"))
    )
    (comp (ref "L7")
      (value "IHLP2020CZER3R3M11")
      (footprint "eagle-import:IHLP-2020BZ-11")
      (libsource (lib "eagle-import") (part "EEZ_inductors_and_transformers_IHLP-2020BZ-11"))
    )
    (comp (ref "NTC1")
      (value "10K/3570K")
      (footprint "eagle-import:R_0805")
      (libsource (lib "eagle-import") (part "NTCR_0805"))
    )
    (comp (ref "OK2")
      (value "TLP291-GB.SE-T")
      (footprint "eagle-import:SO4")
      (libsource (lib "eagle-import") (part "TLP291"))
    )
    (comp (ref "P1")
      (value "T910W-50K")
      (footprint "eagle-import:S64W")
      (libsource (lib "eagle-import") (part "TRIM_EU-S64W"))
    )
    (comp (ref "Q7")
      (value "IRFS4321PBF")
      (footprint "eagle-import:TO263")
      (libsource (lib "eagle-import") (part "N-MOSFETTO263"))
    )
    (comp (ref "Q8")
      (value "IRFS4321PBF")
      (footprint "eagle-import:TO263")
      (libsource (lib "eagle-import") (part "N-MOSFETTO263"))
    )
    (comp (ref "R54")
      (value "100R")
      (footprint "eagle-import:R0805")
      (libsource (lib "eagle-import") (part "R-EU_R0805"))
    )
    (comp (ref "R55")
      (value "N.C.")
      (footprint "eagle-import:R1210")
      (libsource (lib "eagle-import") (part "R-EU_R1210"))
    )
    (comp (ref "R56")
      (value "22R/3W")
      (footprint "eagle-import:R2512")
      (libsource (lib "eagle-import") (part "R-EU_R2512"))
    )
    (comp (ref "R57")
      (value "22R/3W")
      (footprint "eagle-import:R2512")
      (libsource (lib "eagle-import") (part "R-EU_R2512"))
    )
    (comp (ref "R58")
      (value "3R3")
      (footprint "eagle-import:R0805")
      (libsource (lib "eagle-import") (part "R-EU_R0805"))
    )
    (comp (ref "R59")
      (value "10R")
      (footprint "eagle-import:R0805")
      (libsource (lib "eagle-import") (part "R-EU_R0805"))
    )
    (comp (ref "R60")
      (value "47K")
      (footprint "eagle-import:R0805")
      (libsource (lib "eagle-import") (part "R-EU_R0805"))
    )
    (comp (ref "R61")
      (value "3R3")
      (footprint "eagle-import:R0805")
      (libsource (lib "eagle-import") (part "R-EU_R0805"))
    )
    (comp (ref "R62")
      (value "22R/3W")
      (footprint "eagle-import:R2512")
      (libsource (lib "eagle-import") (part "R-EU_R2512"))
    )
    (comp (ref "R63")
      (value "22R/3W")
      (footprint "eagle-import:R2512")
      (libsource (lib "eagle-import") (part "R-EU_R2512"))
    )
    (comp (ref "R64")
      (value "10K")
      (footprint "eagle-import:R0805")
      (libsource (lib "eagle-import") (part "R-EU_R0805"))
    )
    (comp (ref "R65")
      (value "316K")
      (footprint "eagle-import:R0805")
      (libsource (lib "eagle-import") (part "R-EU_R0805"))
    )
    (comp (ref "R66")
      (value "10K")
      (footprint "eagle-import:R0805")
      (libsource (lib "eagle-import") (part "R-EU_R0805"))
    )
    (comp (ref "R67")
      (value "750R")
      (footprint "eagle-import:R0805")
      (libsource (lib "eagle-import") (part "R-EU_R0805"))
    )
    (comp (ref "R68")
      (value "0R")
      (footprint "eagle-import:R0805")
      (libsource (lib "eagle-import") (part "R-EU_R0805"))
    )
    (comp (ref "R69")
      (value "750R")
      (footprint "eagle-import:R0805")
      (libsource (lib "eagle-import") (part "R-EU_R0805"))
    )
    (comp (ref "R70")
      (value "470R")
      (footprint "eagle-import:R0805")
      (libsource (lib "eagle-import") (part "R-EU_R0805"))
    )
    (comp (ref "R71")
      (value "12K")
      (footprint "eagle-import:R0805")
      (libsource (lib "eagle-import") (part "R-EU_R0805"))
    )
    (comp (ref "R72")
      (value "3K3")
      (footprint "eagle-import:R0805")
      (libsource (lib "eagle-import") (part "R-EU_R0805"))
    )
    (comp (ref "R73")
      (value "750R")
      (footprint "eagle-import:R0805")
      (libsource (lib "eagle-import") (part "R-EU_R0805"))
    )
    (comp (ref "R74")
      (value "30K")
      (footprint "eagle-import:R0805")
      (libsource (lib "eagle-import") (part "R-EU_R0805"))
    )
    (comp (ref "R75")
      (value "10K")
      (footprint "eagle-import:R0805")
      (libsource (lib "eagle-import") (part "R-EU_R0805"))
    )
    (comp (ref "R76")
      (value "16K")
      (footprint "eagle-import:R0805")
      (libsource (lib "eagle-import") (part "R-EU_R0805"))
    )
    (comp (ref "R77")
      (value "220R")
      (footprint "eagle-import:R0805")
      (libsource (lib "eagle-import") (part "R-EU_R0805"))
    )
    (comp (ref "R78")
      (value "N.C.")
      (footprint "eagle-import:R0805")
      (libsource (lib "eagle-import") (part "R-EU_R0805"))
    )
    (comp (ref "R79")
      (value "N.C.")
      (footprint "eagle-import:R0805")
      (libsource (lib "eagle-import") (part "R-EU_R0805"))
    )
    (comp (ref "R80")
      (value "3K9")
      (footprint "eagle-import:R0805")
      (libsource (lib "eagle-import") (part "R-EU_R0805"))
    )
    (comp (ref "R81")
      (value "82K")
      (footprint "eagle-import:R0805")
      (libsource (lib "eagle-import") (part "R-EU_R0805"))
    )
    (comp (ref "R82")
      (value "27K")
      (footprint "eagle-import:R0805")
      (libsource (lib "eagle-import") (part "R-EU_R0805"))
    )
    (comp (ref "R83")
      (value "N.C.")
      (footprint "eagle-import:R0805")
      (libsource (lib "eagle-import") (part "R-EU_R0805"))
    )
    (comp (ref "R84")
      (value "10K")
      (footprint "eagle-import:R0805")
      (libsource (lib "eagle-import") (part "R-EU_R0805"))
    )
    (comp (ref "SH2")
      (value "SHORTNOHOLE")
      (footprint "eagle-import:SHORT_NOHOLE")
      (libsource (lib "eagle-import") (part "SHORTNOHOLE"))
    )
    (comp (ref "SH3")
      (value "SHORTNOHOLE")
      (footprint "eagle-import:SHORT_NOHOLE")
      (libsource (lib "eagle-import") (part "SHORTNOHOLE"))
    )
    (comp (ref "TP7")
      (value "TEST_POINT-2")
      (footprint "eagle-import:TP_1.1MM_2")
      (libsource (lib "eagle-import") (part "TEST_POINT-2"))
    )
    (comp (ref "TP8")
      (value "PCB_TEST_TABSHIELD")
      (footprint "eagle-import:PCB_SHIELD_TAB")
      (libsource (lib "eagle-import") (part "PCB_TEST_TABSHIELD"))
    )
    (comp (ref "X4")
      (value "39-28-1023")
      (footprint "eagle-import:MINIFIT_5566-02A")
      (libsource (lib "eagle-import") (part "MINIFIT_5566-02A"))
    )
    (comp (ref "ZD6")
      (value "SMAJ58A-TR")
      (footprint "eagle-import:DO214AC")
      (libsource (lib "eagle-import") (part "PSMAXX"))
    )
  )
  (nets
    (net (code "1") (name "+2.5VREF") (class "Default")
      (node (ref "C72") (pin "1") (pinfunction "1_1") (pintype "passive"))
      (node (ref "IC8") (pin "3") (pinfunction "+IN1_3") (pintype "input"))
      (node (ref "NTC1") (pin "1") (pinfunction "P$1_1") (pintype "bidirectional"))
      (node (ref "P1") (pin "E") (pinfunction "E_E") (pintype "passive"))
      (node (ref "R66") (pin "2") (pinfunction "2_2") (pintype "passive"))
      (node (ref "R72") (pin "1") (pinfunction "1_1") (pintype "passive"))
      (node (ref "R80") (pin "2") (pinfunction "2_2") (pintype "passive"))
    )
    (net (code "2") (name "+6V") (class "Default")
      (node (ref "C22") (pin "1") (pinfunction "1_1") (pintype "passive"))
      (node (ref "C25") (pin "1") (pinfunction "1_1") (pintype "passive"))
      (node (ref "D7") (pin "C") (pinfunction "C_C") (pintype "passive"))
      (node (ref "IC2") (pin "8") (pinfunction "IN_8") (pintype "power_in"))
      (node (ref "L4") (pin "2") (pinfunction "2_2") (pintype "passive"))
      (node (ref "LED1") (pin "A") (pinfunction "A_A") (pintype "passive"))
      (node (ref "R22") (pin "2") (pinfunction "2_2") (pintype "passive"))
      (node (ref "R59") (pin "1") (pinfunction "1_1") (pintype "passive"))
    )
    (net (code "3") (name "+12V") (class "Default")
      (node (ref "C29") (pin "2") (pinfunction "2_2") (pintype "passive"))
      (node (ref "C30") (pin "2") (pinfunction "2_2") (pintype "passive"))
      (node (ref "C4") (pin "1") (pinfunction "1_1") (pintype "passive"))
      (node (ref "Q1") (pin "3") (pinfunction "E_3") (pintype "passive"))
      (node (ref "R26") (pin "2") (pinfunction "2_2") (pintype "passive"))
      (node (ref "R36") (pin "2") (pinfunction "2_2") (pintype "passive"))
      (node (ref "R43") (pin "2") (pinfunction "2_2") (pintype "passive"))
      (node (ref "X1") (pin "1") (pinfunction "1_1") (pintype "passive"))
    )
    (net (code "4") (name "0V") (class "Default")
      (node (ref "C13") (pin "-") (pinfunction "-_-") (pintype "passive"))
      (node (ref "C20") (pin "1") (pinfunction "1_1") (pintype "passive"))
      (node (ref "C27") (pin "2") (pinfunction "2_2") (pintype "passive"))
      (node (ref "C28") (pin "2") (pinfunction "2_2") (pintype "passive"))
      (node (ref "C29") (pin "1") (pinfunction "1_1") (pintype "passive"))
      (node (ref "C30") (pin "1") (pinfunction "1_1") (pintype "passive"))
      (node (ref "C31") (pin "-") (pinfunction "-_-") (pintype "passive"))
      (node (ref "C32") (pin "-") (pinfunction "-_-") (pintype "passive"))
      (node (ref "C36") (pin "1") (pinfunction "1_1") (pintype "passive"))
      (node (ref "C38") (pin "2") (pinfunction "2_2") (pintype "passive"))
      (node (ref "C39") (pin "2") (pinfunction "2_2") (pintype "passive"))
      (node (ref "C4") (pin "2") (pinfunction "2_2") (pintype "passive"))
      (node (ref "C40") (pin "2") (pinfunction "2_2") (pintype "passive"))
      (node (ref "C43") (pin "2") (pinfunction "2_2") (pintype "passive"))
      (node (ref "C44") (pin "2") (pinfunction "2_2") (pintype "passive"))
      (node (ref "C46") (pin "1") (pinfunction "1_1") (pintype "passive"))
      (node (ref "C47") (pin "1") (pinfunction "1_1") (pintype "passive"))
      (node (ref "C7") (pin "2") (pinfunction "-_2") (pintype "passive"))
      (node (ref "C8") (pin "2") (pinfunction "2_2") (pintype "passive"))
      (node (ref "D11") (pin "A") (pinfunction "A_A") (pintype "passive"))
      (node (ref "D15") (pin "2") (pinfunction "A_2") (pintype "passive"))
      (node (ref "IC3") (pin "1") (pinfunction "GND_1") (pintype "passive"))
      (node (ref "IC3") (pin "2") (pinfunction "GND_2") (pintype "passive"))
      (node (ref "IC3") (pin "3") (pinfunction "GND_3") (pintype "passive"))
      (node (ref "IC3") (pin "4") (pinfunction "GND_4") (pintype "passive"))
      (node (ref "IC4") (pin "9") (pinfunction "GNDB_9") (pintype "power_in"))
      (node (ref "JP2") (pin "NC") (pinfunction "NC_NC") (pintype "passive"))
      (node (ref "JP3") (pin "1") (pinfunction "1_1") (pintype "passive"))
      (node (ref "OK1") (pin "3") (pinfunction "EMIT_3") (pintype "passive"))
      (node (ref "Q3") (pin "S") (pinfunction "S_S") (pintype "passive"))
      (node (ref "Q4") (pin "S") (pinfunction "S_S") (pintype "passive"))
      (node (ref "Q5") (pin "S") (pinfunction "S_S") (pintype "passive"))
      (node (ref "R19") (pin "1") (pinfunction "1_1") (pintype "passive"))
      (node (ref "R20") (pin "2") (pinfunction "2_2") (pintype "passive"))
      (node (ref "R21") (pin "2") (pinfunction "2_2") (pintype "passive"))
      (node (ref "R37") (pin "2") (pinfunction "2_2") (pintype "passive"))
      (node (ref "R39") (pin "1") (pinfunction "1_1") (pintype "passive"))
      (node (ref "R39") (pin "2") (pinfunction "2_2") (pintype "passive"))
      (node (ref "SH1") (pin "P$2") (pinfunction "GND_B_P$2") (pintype "bidirectional"))
      (node (ref "TP1") (pin "1") (pinfunction "P$1_1") (pintype "bidirectional"))
      (node (ref "TP4") (pin "1") (pinfunction "P$1_1") (pintype "bidirectional"))
      (node (ref "TR1") (pin "6") (pinfunction "S_BIAS_6") (pintype "passive"))
      (node (ref "X1") (pin "2") (pinfunction "1_2") (pintype "passive"))
      (node (ref "ZD1") (pin "A") (pinfunction "A_A") (pintype "passive"))
      (node (ref "ZD2") (pin "A") (pinfunction "A_A") (pintype "passive"))
    )
    (net (code "5") (name "AGND") (class "Default")
      (node (ref "C37") (pin "1") (pinfunction "1_1") (pintype "passive"))
      (node (ref "C42") (pin "2") (pinfunction "2_2") (pintype "passive"))
      (node (ref "C45") (pin "1") (pinfunction "1_1") (pintype "passive"))
      (node (ref "C48") (pin "1") (pinfunction "1_1") (pintype "passive"))
      (node (ref "C49") (pin "1") (pinfunction "1_1") (pintype "passive"))
      (node (ref "C50") (pin "1") (pinfunction "1_1") (pintype "passive"))
      (node (ref "C51") (pin "1") (pinfunction "1_1") (pintype "passive"))
      (node (ref "IC4") (pin "4") (pinfunction "GNDI_4") (pintype "power_in"))
      (node (ref "IC4") (pin "5") (pinfunction "DISABLE_5") (pintype "input"))
      (node (ref "IC5") (pin "10") (pinfunction "PGND_10") (pintype "power_in"))
      (node (ref "IC5") (pin "11") (pinfunction "AGND_11") (pintype "power_in"))
      (node (ref "IC5") (pin "2") (pinfunction "FB_2") (pintype "input"))
      (node (ref "JP3") (pin "2") (pinfunction "2_2") (pintype "passive"))
      (node (ref "OK2") (pin "3") (pinfunction "EMIT_3") (pintype "passive"))
      (node (ref "Q6") (pin "C") (pinfunction "C_C") (pintype "passive"))
      (node (ref "R23") (pin "2") (pinfunction "2_2") (pintype "passive"))
      (node (ref "R24") (pin "2") (pinfunction "2_2") (pintype "passive"))
      (node (ref "R25") (pin "2") (pinfunction "2_2") (pintype "passive"))
      (node (ref "R32") (pin "1") (pinfunction "1_1") (pintype "passive"))
      (node (ref "R32") (pin "2") (pinfunction "2_2") (pintype "passive"))
      (node (ref "R33") (pin "1") (pinfunction "1_1") (pintype "passive"))
      (node (ref "R45") (pin "2") (pinfunction "2_2") (pintype "passive"))
      (node (ref "R48") (pin "2") (pinfunction "2_2") (pintype "passive"))
      (node (ref "R49") (pin "2") (pinfunction "2_2") (pintype "passive"))
      (node (ref "R52") (pin "2") (pinfunction "2_2") (pintype "passive"))
      (node (ref "TR2") (pin "1") (pinfunction "S_DOT_1") (pintype "passive"))
      (node (ref "ZD4") (pin "A") (pinfunction "A_A") (pintype "passive"))
      (node (ref "ZD5") (pin "A") (pinfunction "A_A") (pintype "passive"))
    )
    (net (code "6") (name "AUX") (class "Default")
      (node (ref "C3") (pin "2") (pinfunction "2_2") (pintype "passive"))
      (node (ref "D1") (pin "A") (pinfunction "A_A") (pintype "passive"))
      (node (ref "D10") (pin "A") (pinfunction "A_A") (pintype "passive"))
      (node (ref "R16") (pin "2") (pinfunction "2_2") (pintype "passive"))
      (node (ref "TR1") (pin "7") (pinfunction "S_BIAS_DOT_7") (pintype "passive"))
    )
    (net (code "7") (name "AUX_OUT") (class "Default")
      (node (ref "C20") (pin "2") (pinfunction "2_2") (pintype "passive"))
      (node (ref "C7") (pin "1") (pinfunction "+_1") (pintype "passive"))
      (node (ref "IC3") (pin "5") (pinfunction "VDD_5") (pintype "power_in"))
      (node (ref "Q1") (pin "2") (pinfunction "C_2") (pintype "passive"))
      (node (ref "Q1") (pin "4") (pinfunction "C_4") (pintype "passive"))
      (node (ref "R4") (pin "2") (pinfunction "2_2") (pintype "passive"))
      (node (ref "R5") (pin "1") (pinfunction "1_1") (pintype "passive"))
      (node (ref "ZD1") (pin "C") (pinfunction "C_C") (pintype "passive"))
    )
    (net (code "8") (name "BUCK_OUT") (class "Default")
      (node (ref "C33") (pin "2") (pinfunction "2_2") (pintype "passive"))
      (node (ref "C34") (pin "2") (pinfunction "2_2") (pintype "passive"))
      (node (ref "C35") (pin "2") (pinfunction "2_2") (pintype "passive"))
      (node (ref "D15") (pin "1") (pinfunction "C_1") (pintype "passive"))
      (node (ref "IC4") (pin "14") (pinfunction "GNDA_14") (pintype "power_in"))
      (node (ref "L5") (pin "2") (pinfunction "P$2_2") (pintype "bidirectional"))
      (node (ref "L6") (pin "2") (pinfunction "P$2_2") (pintype "bidirectional"))
      (node (ref "Q2") (pin "S") (pinfunction "S_S") (pintype "passive"))
      (node (ref "Q3") (pin "D") (pinfunction "D_D") (pintype "passive"))
      (node (ref "TP3") (pin "1") (pinfunction "P$1_1") (pintype "bidirectional"))
    )
    (net (code "9") (name "CT_OUT") (class "Default")
      (node (ref "D12") (pin "C") (pinfunction "C_C") (pintype "passive"))
      (node (ref "R24") (pin "1") (pinfunction "1_1") (pintype "passive"))
      (node (ref "R25") (pin "1") (pinfunction "1_1") (pintype "passive"))
      (node (ref "R51") (pin "1") (pinfunction "1_1") (pintype "passive"))
    )
    (net (code "10") (name "DC_BUS") (class "Default")
      (node (ref "B1") (pin "+") (pinfunction "+_+") (pintype "passive"))
      (node (ref "C12") (pin "1") (pinfunction "1_1") (pintype "passive"))
      (node (ref "C13") (pin "+") (pinfunction "+_+") (pintype "passive"))
      (node (ref "C31") (pin "+") (pinfunction "+_+") (pintype "passive"))
      (node (ref "C32") (pin "+") (pinfunction "+_+") (pintype "passive"))
      (node (ref "C36") (pin "2") (pinfunction "2_2") (pintype "passive"))
      (node (ref "R38") (pin "1") (pinfunction "1_1") (pintype "passive"))
      (node (ref "R40") (pin "2") (pinfunction "2_2") (pintype "passive"))
      (node (ref "R41") (pin "2") (pinfunction "2_2") (pintype "passive"))
      (node (ref "R7") (pin "1") (pinfunction "1_1") (pintype "passive"))
      (node (ref "R8") (pin "1") (pinfunction "1_1") (pintype "passive"))
      (node (ref "TR1") (pin "1") (pinfunction "SHIELD_1") (pintype "passive"))
      (node (ref "TR1") (pin "2") (pinfunction "P_2") (pintype "passive"))
      (node (ref "TR2") (pin "7") (pinfunction "P_7") (pintype "passive"))
    )
    (net (code "11") (name "DC_OUT") (class "Default")
      (node (ref "C11") (pin "1") (pinfunction "1_1") (pintype "passive"))
      (node (ref "L2") (pin "2") (pinfunction "2_2") (pintype "passive"))
      (node (ref "X3") (pin "3") (pinfunction "S_3") (pintype "passive"))
    )
    (net (code "12") (name "GND") (class "Default")
      (node (ref "C14") (pin "1") (pinfunction "+_1") (pintype "passive"))
      (node (ref "C15") (pin "1") (pinfunction "1_1") (pintype "passive"))
      (node (ref "C16") (pin "1") (pinfunction "1_1") (pintype "passive"))
      (node (ref "C17") (pin "1") (pinfunction "1_1") (pintype "passive"))
      (node (ref "C19") (pin "2") (pinfunction "2_2") (pintype "passive"))
      (node (ref "C22") (pin "2") (pinfunction "2_2") (pintype "passive"))
      (node (ref "C23") (pin "-") (pinfunction "-_-") (pintype "passive"))
      (node (ref "C24") (pin "-") (pinfunction "-_-") (pintype "passive"))
      (node (ref "C25") (pin "2") (pinfunction "2_2") (pintype "passive"))
      (node (ref "C52") (pin "-") (pinfunction "-_-") (pintype "passive"))
      (node (ref "C53") (pin "-") (pinfunction "-_-") (pintype "passive"))
      (node (ref "C54") (pin "-") (pinfunction "-_-") (pintype "passive"))
      (node (ref "C55") (pin "2") (pinfunction "2_2") (pintype "passive"))
      (node (ref "C56") (pin "2") (pinfunction "2_2") (pintype "passive"))
      (node (ref "C57") (pin "2") (pinfunction "2_2") (pintype "passive"))
      (node (ref "C58") (pin "2") (pinfunction "2_2") (pintype "passive"))
      (node (ref "C59") (pin "2") (pinfunction "2_2") (pintype "passive"))
      (node (ref "C60") (pin "1") (pinfunction "1_1") (pintype "passive"))
      (node (ref "C61") (pin "2") (pinfunction "2_2") (pintype "passive"))
      (node (ref "C62") (pin "2") (pinfunction "2_2") (pintype "passive"))
      (node (ref "C63") (pin "2") (pinfunction "2_2") (pintype "passive"))
      (node (ref "C64") (pin "2") (pinfunction "2_2") (pintype "passive"))
      (node (ref "C65") (pin "2") (pinfunction "2_2") (pintype "passive"))
      (node (ref "C66") (pin "2") (pinfunction "2_2") (pintype "passive"))
      (node (ref "C67") (pin "2") (pinfunction "2_2") (pintype "passive"))
      (node (ref "C71") (pin "-") (pinfunction "-_-") (pintype "passive"))
      (node (ref "C72") (pin "2") (pinfunction "2_2") (pintype "passive"))
      (node (ref "C75") (pin "2") (pinfunction "2_2") (pintype "passive"))
      (node (ref "D3") (pin "C") (pinfunction "C_C") (pintype "passive"))
      (node (ref "D9") (pin "A") (pinfunction "A_A") (pintype "passive"))
      (node (ref "IC1") (pin "5") (pinfunction "GND_5") (pintype "passive"))
      (node (ref "IC10") (pin "1") (pinfunction "E_1") (pintype "passive"))
      (node (ref "IC10") (pin "4") (pinfunction "V-_4") (pintype "power_in"))
      (node (ref "IC2") (pin "4") (pinfunction "GND_4") (pintype "passive"))
      (node (ref "IC6") (pin "6") (pinfunction "VS_6") (pintype "passive"))
      (node (ref "IC6") (pin "7") (pinfunction "GND_7") (pintype "power_in"))
      (node (ref "IC7") (pin "3") (pinfunction "+IN_3") (pintype "input"))
      (node (ref "IC7") (pin "5") (pinfunction "+IN_5") (pintype "input"))
      (node (ref "IC8") (pin "4") (pinfunction "VCC-_4") (pintype "power_in"))
      (node (ref "IC9") (pin "3") (pinfunction "A_3") (pintype "passive"))
      (node (ref "JP1") (pin "NO") (pinfunction "NO_NO") (pintype "passive"))
      (node (ref "P1") (pin "A") (pinfunction "A_A") (pintype "passive"))
      (node (ref "Q7") (pin "2") (pinfunction "S_2") (pintype "passive"))
      (node (ref "Q8") (pin "2") (pinfunction "S_2") (pintype "passive"))
      (node (ref "R13") (pin "2") (pinfunction "2_2") (pintype "passive"))
      (node (ref "R14") (pin "2") (pinfunction "2_2") (pintype "passive"))
      (node (ref "R60") (pin "2") (pinfunction "2_2") (pintype "passive"))
      (node (ref "R82") (pin "2") (pinfunction "2_2") (pintype "passive"))
      (node (ref "R83") (pin "1") (pinfunction "1_1") (pintype "passive"))
      (node (ref "R84") (pin "1") (pinfunction "1_1") (pintype "passive"))
      (node (ref "TP2") (pin "1") (pinfunction "P$1_1") (pintype "bidirectional"))
      (node (ref "TP7") (pin "GND") (pinfunction "GND_GND") (pintype "bidirectional"))
      (node (ref "TR1") (pin "10") (pinfunction "S1_10") (pintype "passive"))
      (node (ref "TR1") (pin "11") (pinfunction "S1_11") (pintype "passive"))
      (node (ref "TR1") (pin "9") (pinfunction "S2_DOT_9") (pintype "passive"))
      (node (ref "X3") (pin "6") (pinfunction "S_6") (pintype "passive"))
      (node (ref "X4") (pin "2") (pinfunction "1_2") (pintype "passive"))
      (node (ref "ZD3") (pin "A") (pinfunction "A_A") (pintype "passive"))
      (node (ref "ZD6") (pin "A") (pinfunction "A_A") (pintype "passive"))
    )
    (net (code "13") (name "GNDA") (class "Default")
      (node (ref "B1") (pin "-") (pinfunction "-_-") (pintype "passive"))
      (node (ref "SH1") (pin "P$1") (pinfunction "GND_A_P$1") (pintype "bidirectional"))
    )
    (net (code "14") (name "HD") (class "Default")
      (node (ref "IC5") (pin "5") (pinfunction "HD_5") (pintype "output"))
      (node (ref "R28") (pin "2") (pinfunction "2_2") (pintype "passive"))
    )
    (net (code "15") (name "HI_OUT") (class "Default")
      (node (ref "D14") (pin "A") (pinfunction "A_A") (pintype "passive"))
      (node (ref "IC4") (pin "15") (pinfunction "VOA_15") (pintype "output"))
      (node (ref "R27") (pin "2") (pinfunction "2_2") (pintype "passive"))
    )
    (net (code "16") (name "ISO_FB") (class "Default")
      (node (ref "C50") (pin "2") (pinfunction "2_2") (pintype "passive"))
      (node (ref "IC5") (pin "3") (pinfunction "COMP_3") (pintype "passive"))
      (node (ref "OK2") (pin "4") (pinfunction "COL_4") (pintype "passive"))
      (node (ref "Q6") (pin "E") (pinfunction "E_E") (pintype "passive"))
      (node (ref "R53") (pin "1") (pinfunction "1_1") (pintype "passive"))
      (node (ref "TP6") (pin "1") (pinfunction "P$1_1") (pintype "bidirectional"))
    )
    (net (code "17") (name "LD") (class "Default")
      (node (ref "IC5") (pin "6") (pinfunction "LD_6") (pintype "output"))
      (node (ref "R30") (pin "2") (pinfunction "2_2") (pintype "passive"))
    )
    (net (code "18") (name "LO_OUT") (class "Default")
      (node (ref "D17") (pin "A") (pinfunction "A_A") (pintype "passive"))
      (node (ref "IC4") (pin "10") (pinfunction "VOB_10") (pintype "output"))
      (node (ref "R34") (pin "1") (pinfunction "1_1") (pintype "passive"))
    )
    (net (code "19") (name "Net-(C3-Pad1)") (class "Default")
      (node (ref "C3") (pin "1") (pinfunction "1_1") (pintype "passive"))
      (node (ref "R2") (pin "2") (pinfunction "2_2") (pintype "passive"))
    )
    (net (code "20") (name "Net-(C9-Pad1)") (class "Default")
      (node (ref "C9") (pin "1") (pinfunction "1_1") (pintype "passive"))
      (node (ref "R6") (pin "2") (pinfunction "2_2") (pintype "passive"))
    )
    (net (code "21") (name "Net-(C10-+)") (class "Default")
      (node (ref "C10") (pin "1") (pinfunction "+_1") (pintype "passive"))
      (node (ref "D2") (pin "C") (pinfunction "C_C") (pintype "passive"))
      (node (ref "L2") (pin "1") (pinfunction "1_1") (pintype "passive"))
      (node (ref "R6") (pin "1") (pinfunction "1_1") (pintype "passive"))
    )
    (net (code "22") (name "Net-(C10--)") (class "Default")
      (node (ref "C10") (pin "2") (pinfunction "-_2") (pintype "passive"))
      (node (ref "C11") (pin "2") (pinfunction "2_2") (pintype "passive"))
      (node (ref "JP1") (pin "COM") (pinfunction "COM_COM") (pintype "passive"))
      (node (ref "TR1") (pin "14") (pinfunction "S3_14") (pintype "passive"))
    )
    (net (code "23") (name "Net-(C12-Pad2)") (class "Default")
      (node (ref "C12") (pin "2") (pinfunction "2_2") (pintype "passive"))
      (node (ref "D4") (pin "C") (pinfunction "C_C") (pintype "passive"))
      (node (ref "R7") (pin "2") (pinfunction "2_2") (pintype "passive"))
    )
    (net (code "24") (name "Net-(C14--)") (class "Default")
      (node (ref "C14") (pin "2") (pinfunction "-_2") (pintype "passive"))
      (node (ref "D5") (pin "A") (pinfunction "A_A") (pintype "passive"))
      (node (ref "L3") (pin "1") (pinfunction "1_1") (pintype "passive"))
      (node (ref "R10") (pin "1") (pinfunction "1_1") (pintype "passive"))
    )
    (net (code "25") (name "Net-(C18-Pad1)") (class "Default")
      (node (ref "C18") (pin "1") (pinfunction "1_1") (pintype "passive"))
      (node (ref "R10") (pin "2") (pinfunction "2_2") (pintype "passive"))
    )
    (net (code "26") (name "Net-(C19-Pad1)") (class "Default")
      (node (ref "C19") (pin "1") (pinfunction "1_1") (pintype "passive"))
      (node (ref "JP2") (pin "COM") (pinfunction "COM_COM") (pintype "passive"))
    )
    (net (code "27") (name "Net-(C21-Pad1)") (class "Default")
      (node (ref "C21") (pin "1") (pinfunction "1_1") (pintype "passive"))
      (node (ref "R11") (pin "2") (pinfunction "2_2") (pintype "passive"))
    )
    (net (code "28") (name "Net-(C21-Pad2)") (class "Default")
      (node (ref "C21") (pin "2") (pinfunction "2_2") (pintype "passive"))
      (node (ref "D8") (pin "A") (pinfunction "A_A") (pintype "passive"))
      (node (ref "TR1") (pin "12") (pinfunction "S1_DOT_12") (pintype "passive"))
      (node (ref "TR1") (pin "13") (pinfunction "S1_DOT_13") (pintype "passive"))
    )
    (net (code "29") (name "Net-(C24-Pad+)") (class "Default")
      (node (ref "C24") (pin "+") (pinfunction "+_+") (pintype "passive"))
      (node (ref "D8") (pin "C") (pinfunction "C_C") (pintype "passive"))
      (node (ref "L4") (pin "1") (pinfunction "1_1") (pintype "passive"))
      (node (ref "R11") (pin "1") (pinfunction "1_1") (pintype "passive"))
      (node (ref "R18") (pin "1") (pinfunction "1_1") (pintype "passive"))
    )
    (net (code "30") (name "Net-(C26-Pad1)") (class "Default")
      (node (ref "C26") (pin "1") (pinfunction "1_1") (pintype "passive"))
      (node (ref "R21") (pin "1") (pinfunction "1_1") (pintype "passive"))
    )
    (net (code "31") (name "Net-(C41-Pad1)") (class "Default")
      (node (ref "C41") (pin "1") (pinfunction "1_1") (pintype "passive"))
      (node (ref "R31") (pin "1") (pinfunction "1_1") (pintype "passive"))
    )
    (net (code "32") (name "Net-(C46-Pad2)") (class "Default")
      (node (ref "C46") (pin "2") (pinfunction "2_2") (pintype "passive"))
      (node (ref "C47") (pin "2") (pinfunction "2_2") (pintype "passive"))
      (node (ref "D18") (pin "1") (pinfunction "C_1") (pintype "passive"))
      (node (ref "D18") (pin "3") (pinfunction "C_3") (pintype "passive"))
      (node (ref "D19") (pin "1") (pinfunction "C_1") (pintype "passive"))
      (node (ref "D19") (pin "3") (pinfunction "C_3") (pintype "passive"))
      (node (ref "R40") (pin "1") (pinfunction "1_1") (pintype "passive"))
      (node (ref "R41") (pin "1") (pinfunction "1_1") (pintype "passive"))
    )
    (net (code "33") (name "Net-(C51-Pad2)") (class "Default")
      (node (ref "C51") (pin "2") (pinfunction "2_2") (pintype "passive"))
      (node (ref "R53") (pin "2") (pinfunction "2_2") (pintype "passive"))
    )
    (net (code "34") (name "Net-(C60-Pad2)") (class "Default")
      (node (ref "C60") (pin "2") (pinfunction "2_2") (pintype "passive"))
      (node (ref "R55") (pin "1") (pinfunction "1_1") (pintype "passive"))
    )
    (net (code "35") (name "Net-(C61-Pad1)") (class "Default")
      (node (ref "C61") (pin "1") (pinfunction "1_1") (pintype "passive"))
      (node (ref "R56") (pin "2") (pinfunction "2_2") (pintype "passive"))
      (node (ref "R57") (pin "2") (pinfunction "2_2") (pintype "passive"))
    )
    (net (code "36") (name "Net-(C65-Pad1)") (class "Default")
      (node (ref "C65") (pin "1") (pinfunction "1_1") (pintype "passive"))
      (node (ref "R62") (pin "2") (pinfunction "2_2") (pintype "passive"))
      (node (ref "R63") (pin "2") (pinfunction "2_2") (pintype "passive"))
    )
    (net (code "37") (name "Net-(C70-Pad2)") (class "Default")
      (node (ref "C70") (pin "2") (pinfunction "2_2") (pintype "passive"))
      (node (ref "R74") (pin "2") (pinfunction "2_2") (pintype "passive"))
    )
    (net (code "38") (name "Net-(C71-Pad+)") (class "Default")
      (node (ref "C71") (pin "+") (pinfunction "+_+") (pintype "passive"))
      (node (ref "R67") (pin "1") (pinfunction "1_1") (pintype "passive"))
      (node (ref "R76") (pin "1") (pinfunction "1_1") (pintype "passive"))
      (node (ref "R77") (pin "1") (pinfunction "1_1") (pintype "passive"))
    )
    (net (code "39") (name "Net-(C74-Pad2)") (class "Default")
      (node (ref "C74") (pin "2") (pinfunction "2_2") (pintype "passive"))
      (node (ref "R79") (pin "1") (pinfunction "1_1") (pintype "passive"))
    )
    (net (code "40") (name "Net-(D1-PadC)") (class "Default")
      (node (ref "D1") (pin "C") (pinfunction "C_C") (pintype "passive"))
      (node (ref "R2") (pin "1") (pinfunction "1_1") (pintype "passive"))
      (node (ref "R4") (pin "1") (pinfunction "1_1") (pintype "passive"))
    )
    (net (code "41") (name "Net-(D10-PadC)") (class "Default")
      (node (ref "D10") (pin "C") (pinfunction "C_C") (pintype "passive"))
      (node (ref "D11") (pin "C") (pinfunction "C_C") (pintype "passive"))
      (node (ref "R17") (pin "2") (pinfunction "2_2") (pintype "passive"))
    )
    (net (code "42") (name "Net-(D13-A)") (class "Default")
      (node (ref "D13") (pin "2") (pinfunction "A_2") (pintype "passive"))
      (node (ref "R26") (pin "1") (pinfunction "1_1") (pintype "passive"))
    )
    (net (code "43") (name "Net-(D14-PadC)") (class "Default")
      (node (ref "D14") (pin "C") (pinfunction "C_C") (pintype "passive"))
      (node (ref "Q2") (pin "G") (pinfunction "G_G") (pintype "passive"))
      (node (ref "R27") (pin "1") (pinfunction "1_1") (pintype "passive"))
    )
    (net (code "44") (name "Net-(D16-PadA)") (class "Default")
      (node (ref "D16") (pin "A") (pinfunction "A_A") (pintype "passive"))
      (node (ref "R36") (pin "1") (pinfunction "1_1") (pintype "passive"))
    )
    (net (code "45") (name "Net-(D17-PadC)") (class "Default")
      (node (ref "D17") (pin "C") (pinfunction "C_C") (pintype "passive"))
      (node (ref "Q3") (pin "G") (pinfunction "G_G") (pintype "passive"))
      (node (ref "R34") (pin "2") (pinfunction "2_2") (pintype "passive"))
      (node (ref "R37") (pin "1") (pinfunction "1_1") (pintype "passive"))
    )
    (net (code "46") (name "Net-(D18-A)") (class "Default")
      (node (ref "C41") (pin "2") (pinfunction "2_2") (pintype "passive"))
      (node (ref "D18") (pin "2") (pinfunction "A_2") (pintype "passive"))
      (node (ref "L6") (pin "1") (pinfunction "P$1_1") (pintype "bidirectional"))
      (node (ref "Q5") (pin "D") (pinfunction "D_D") (pintype "passive"))
      (node (ref "TR3") (pin "P1_DOT") (pinfunction "P_DOT_P1_DOT") (pintype "passive"))
    )
    (net (code "47") (name "Net-(D19-A)") (class "Default")
      (node (ref "D19") (pin "2") (pinfunction "A_2") (pintype "passive"))
      (node (ref "L5") (pin "1") (pinfunction "P$1_1") (pintype "bidirectional"))
      (node (ref "Q4") (pin "D") (pinfunction "D_D") (pintype "passive"))
      (node (ref "R29") (pin "2") (pinfunction "2_2") (pintype "passive"))
      (node (ref "TR3") (pin "P1") (pinfunction "P_P1") (pintype "passive"))
    )
    (net (code "48") (name "Net-(D20-PadC)") (class "Default")
      (node (ref "D20") (pin "C") (pinfunction "C_C") (pintype "passive"))
      (node (ref "Q4") (pin "G") (pinfunction "G_G") (pintype "passive"))
      (node (ref "R46") (pin "1") (pinfunction "1_1") (pintype "passive"))
    )
    (net (code "49") (name "Net-(D21-PadC)") (class "Default")
      (node (ref "D21") (pin "C") (pinfunction "C_C") (pintype "passive"))
      (node (ref "Q5") (pin "G") (pinfunction "G_G") (pintype "passive"))
      (node (ref "R47") (pin "1") (pinfunction "1_1") (pintype "passive"))
    )
    (net (code "50") (name "Net-(IC2-FB)") (class "Default")
      (node (ref "IC2") (pin "7") (pinfunction "FB_7") (pintype "input"))
      (node (ref "R12") (pin "2") (pinfunction "2_2") (pintype "passive"))
      (node (ref "R13") (pin "1") (pinfunction "1_1") (pintype "passive"))
    )
    (net (code "51") (name "Net-(IC3-BR)") (class "Default")
      (node (ref "IC3") (pin "8") (pinfunction "BR_8") (pintype "input"))
      (node (ref "R20") (pin "1") (pinfunction "1_1") (pintype "passive"))
      (node (ref "R9") (pin "2") (pinfunction "2_2") (pintype "passive"))
    )
    (net (code "52") (name "Net-(IC3-FB)") (class "Default")
      (node (ref "C26") (pin "2") (pinfunction "2_2") (pintype "passive"))
      (node (ref "C28") (pin "1") (pinfunction "1_1") (pintype "passive"))
      (node (ref "IC3") (pin "7") (pinfunction "FB_7") (pintype "input"))
      (node (ref "OK1") (pin "4") (pinfunction "COL_4") (pintype "passive"))
    )
    (net (code "53") (name "Net-(IC3-ZCD)") (class "Default")
      (node (ref "C27") (pin "1") (pinfunction "1_1") (pintype "passive"))
      (node (ref "IC3") (pin "6") (pinfunction "ZCD_6") (pintype "input"))
      (node (ref "R16") (pin "1") (pinfunction "1_1") (pintype "passive"))
      (node (ref "R17") (pin "1") (pinfunction "1_1") (pintype "passive"))
      (node (ref "R19") (pin "2") (pinfunction "2_2") (pintype "passive"))
    )
    (net (code "54") (name "Net-(IC4-DT)") (class "Default")
      (node (ref "IC4") (pin "6") (pinfunction "DT_6") (pintype "input"))
      (node (ref "R33") (pin "2") (pinfunction "2_2") (pintype "passive"))
    )
    (net (code "55") (name "Net-(IC4-VDDA)") (class "Default")
      (node (ref "C33") (pin "1") (pinfunction "1_1") (pintype "passive"))
      (node (ref "C34") (pin "1") (pinfunction "1_1") (pintype "passive"))
      (node (ref "C35") (pin "1") (pinfunction "1_1") (pintype "passive"))
      (node (ref "D13") (pin "1") (pinfunction "C_1") (pintype "passive"))
      (node (ref "D13") (pin "3") (pinfunction "C_3") (pintype "passive"))
      (node (ref "IC4") (pin "16") (pinfunction "VDDA_16") (pintype "power_in"))
    )
    (net (code "56") (name "Net-(IC4-VDDB)") (class "Default")
      (node (ref "C38") (pin "1") (pinfunction "1_1") (pintype "passive"))
      (node (ref "C39") (pin "1") (pinfunction "1_1") (pintype "passive"))
      (node (ref "C40") (pin "1") (pinfunction "1_1") (pintype "passive"))
      (node (ref "D16") (pin "C") (pinfunction "C_C") (pintype "passive"))
      (node (ref "IC4") (pin "11") (pinfunction "VDDB_11") (pintype "power_in"))
    )
    (net (code "57") (name "Net-(IC4-VIA)") (class "Default")
      (node (ref "IC4") (pin "1") (pinfunction "VIA_1") (pintype "input"))
      (node (ref "R28") (pin "1") (pinfunction "1_1") (pintype "passive"))
    )
    (net (code "58") (name "Net-(IC4-VIB)") (class "Default")
      (node (ref "IC4") (pin "2") (pinfunction "VIB_2") (pintype "input"))
      (node (ref "R30") (pin "1") (pinfunction "1_1") (pintype "passive"))
    )
    (net (code "59") (name "Net-(IC5-CS)") (class "Default")
      (node (ref "C49") (pin "2") (pinfunction "2_2") (pintype "passive"))
      (node (ref "IC5") (pin "12") (pinfunction "CS_12") (pintype "input"))
      (node (ref "R51") (pin "2") (pinfunction "2_2") (pintype "passive"))
    )
    (net (code "60") (name "Net-(IC5-REF)") (class "Default")
      (node (ref "C48") (pin "2") (pinfunction "2_2") (pintype "passive"))
      (node (ref "IC5") (pin "4") (pinfunction "REF_4") (pintype "output"))
      (node (ref "R35") (pin "1") (pinfunction "1_1") (pintype "passive"))
      (node (ref "R50") (pin "1") (pinfunction "1_1") (pintype "passive"))
    )
    (net (code "61") (name "Net-(IC5-RT{slash}SYNC)") (class "Default")
      (node (ref "IC5") (pin "15") (pinfunction "RT/SYNC_15") (pintype "input"))
      (node (ref "R49") (pin "1") (pinfunction "1_1") (pintype "passive"))
    )
    (net (code "62") (name "Net-(IC5-SS)") (class "Default")
      (node (ref "C45") (pin "2") (pinfunction "2_2") (pintype "passive"))
      (node (ref "IC5") (pin "13") (pinfunction "SS_13") (pintype "passive"))
    )
    (net (code "63") (name "Net-(IC5-TIME)") (class "Default")
      (node (ref "IC5") (pin "14") (pinfunction "TIME_14") (pintype "input"))
      (node (ref "R48") (pin "1") (pinfunction "1_1") (pintype "passive"))
    )
    (net (code "64") (name "Net-(IC5-UVLO)") (class "Default")
      (node (ref "IC5") (pin "16") (pinfunction "UVLO_16") (pintype "input"))
      (node (ref "R44") (pin "1") (pinfunction "1_1") (pintype "passive"))
      (node (ref "ZD5") (pin "C") (pinfunction "C_C") (pintype "passive"))
    )
    (net (code "65") (name "Net-(IC5-VCC)") (class "Default")
      (node (ref "C43") (pin "1") (pinfunction "1_1") (pintype "passive"))
      (node (ref "C44") (pin "1") (pinfunction "1_1") (pintype "passive"))
      (node (ref "IC5") (pin "1") (pinfunction "VIN_1") (pintype "input"))
      (node (ref "IC5") (pin "7") (pinfunction "VCC_7") (pintype "power_in"))
      (node (ref "R43") (pin "1") (pinfunction "1_1") (pintype "passive"))
    )
    (net (code "66") (name "Net-(IC6-GATE1)") (class "Default")
      (node (ref "D22") (pin "C") (pinfunction "C_C") (pintype "passive"))
      (node (ref "IC6") (pin "1") (pinfunction "GATE1_1") (pintype "output"))
      (node (ref "R58") (pin "2") (pinfunction "2_2") (pintype "passive"))
    )
    (net (code "67") (name "Net-(IC6-GATE2)") (class "Default")
      (node (ref "D23") (pin "C") (pinfunction "C_C") (pintype "passive"))
      (node (ref "IC6") (pin "8") (pinfunction "GATE2_8") (pintype "output"))
      (node (ref "R61") (pin "2") (pinfunction "2_2") (pintype "passive"))
    )
    (net (code "68") (name "Net-(IC6-MOT)") (class "Default")
      (node (ref "IC6") (pin "3") (pinfunction "MOT_3") (pintype "passive"))
      (node (ref "R60") (pin "1") (pinfunction "1_1") (pintype "passive"))
    )
    (net (code "69") (name "Net-(IC6-VCC)") (class "Default")
      (node (ref "C62") (pin "1") (pinfunction "1_1") (pintype "passive"))
      (node (ref "C63") (pin "1") (pinfunction "1_1") (pintype "passive"))
      (node (ref "IC6") (pin "2") (pinfunction "VCC_2") (pintype "power_in"))
      (node (ref "R59") (pin "2") (pinfunction "2_2") (pintype "passive"))
    )
    (net (code "70") (name "Net-(IC7A--IN)") (class "Default")
      (node (ref "C68") (pin "2") (pinfunction "2_2") (pintype "passive"))
      (node (ref "IC7") (pin "2") (pinfunction "-IN_2") (pintype "input"))
      (node (ref "R68") (pin "2") (pinfunction "2_2") (pintype "passive"))
      (node (ref "R69") (pin "1") (pinfunction "1_1") (pintype "passive"))
      (node (ref "R73") (pin "1") (pinfunction "1_1") (pintype "passive"))
    )
    (net (code "71") (name "Net-(IC7A-OUT)") (class "Default")
      (node (ref "C68") (pin "1") (pinfunction "1_1") (pintype "passive"))
      (node (ref "IC7") (pin "1") (pinfunction "OUT_1") (pintype "output"))
      (node (ref "R77") (pin "2") (pinfunction "2_2") (pintype "passive"))
    )
    (net (code "72") (name "Net-(IC7B--IN)") (class "Default")
      (node (ref "IC7") (pin "6") (pinfunction "-IN_6") (pintype "input"))
      (node (ref "R64") (pin "2") (pinfunction "2_2") (pintype "passive"))
      (node (ref "R66") (pin "1") (pinfunction "1_1") (pintype "passive"))
    )
    (net (code "73") (name "Net-(IC7B-OUT)") (class "Default")
      (node (ref "IC7") (pin "7") (pinfunction "OUT_7") (pintype "output"))
      (node (ref "R64") (pin "1") (pinfunction "1_1") (pintype "passive"))
      (node (ref "R69") (pin "2") (pinfunction "2_2") (pintype "passive"))
    )
    (net (code "74") (name "Net-(IC8A--IN1)") (class "Default")
      (node (ref "C69") (pin "2") (pinfunction "2_2") (pintype "passive"))
      (node (ref "IC8") (pin "2") (pinfunction "-IN1_2") (pintype "input"))
      (node (ref "R74") (pin "1") (pinfunction "1_1") (pintype "passive"))
      (node (ref "R75") (pin "1") (pinfunction "1_1") (pintype "passive"))
    )
    (net (code "75") (name "Net-(IC8A-OUT1)") (class "Default")
      (node (ref "C69") (pin "1") (pinfunction "1_1") (pintype "passive"))
      (node (ref "C70") (pin "1") (pinfunction "1_1") (pintype "passive"))
      (node (ref "C73") (pin "1") (pinfunction "1_1") (pintype "passive"))
      (node (ref "C74") (pin "1") (pinfunction "1_1") (pintype "passive"))
      (node (ref "IC8") (pin "1") (pinfunction "OUT1_1") (pintype "output"))
      (node (ref "IC9") (pin "1") (pinfunction "C_1") (pintype "passive"))
      (node (ref "OK2") (pin "2") (pinfunction "C_2") (pintype "passive"))
      (node (ref "R78") (pin "2") (pinfunction "2_2") (pintype "passive"))
    )
    (net (code "76") (name "Net-(IC8B-+IN)") (class "Default")
      (node (ref "IC8") (pin "5") (pinfunction "+IN_5") (pintype "input"))
      (node (ref "JP4") (pin "COM") (pinfunction "COM_COM") (pintype "passive"))
    )
    (net (code "77") (name "Net-(IC8B--IN)") (class "Default")
      (node (ref "IC8") (pin "6") (pinfunction "-IN_6") (pintype "input"))
      (node (ref "IC8") (pin "7") (pinfunction "OUT_7") (pintype "output"))
      (node (ref "R73") (pin "2") (pinfunction "2_2") (pintype "passive"))
    )
    (net (code "78") (name "Net-(IC9-REF)") (class "Default")
      (node (ref "C73") (pin "2") (pinfunction "2_2") (pintype "passive"))
      (node (ref "IC9") (pin "2") (pinfunction "REF_2") (pintype "passive"))
      (node (ref "R71") (pin "1") (pinfunction "1_1") (pintype "passive"))
      (node (ref "R75") (pin "2") (pinfunction "2_2") (pintype "passive"))
      (node (ref "R76") (pin "2") (pinfunction "2_2") (pintype "passive"))
      (node (ref "R79") (pin "2") (pinfunction "2_2") (pintype "passive"))
      (node (ref "R83") (pin "2") (pinfunction "2_2") (pintype "passive"))
      (node (ref "TP8") (pin "1") (pinfunction "P$1_1") (pintype "bidirectional"))
    )
    (net (code "79") (name "Net-(IC10A-+IN)") (class "Default")
      (node (ref "IC10") (pin "2") (pinfunction "+IN_2") (pintype "input"))
      (node (ref "R80") (pin "1") (pinfunction "1_1") (pintype "passive"))
      (node (ref "R81") (pin "2") (pinfunction "2_2") (pintype "passive"))
      (node (ref "R82") (pin "1") (pinfunction "1_1") (pintype "passive"))
    )
    (net (code "80") (name "Net-(IC10A--IN)") (class "Default")
      (node (ref "IC10") (pin "3") (pinfunction "-IN_3") (pintype "input"))
      (node (ref "NTC1") (pin "2") (pinfunction "P$2_2") (pintype "bidirectional"))
      (node (ref "R84") (pin "2") (pinfunction "2_2") (pintype "passive"))
    )
    (net (code "81") (name "Net-(JP4-PadNO)") (class "Default")
      (node (ref "JP4") (pin "NO") (pinfunction "NO_NO") (pintype "passive"))
      (node (ref "P1") (pin "S") (pinfunction "S_S") (pintype "passive"))
    )
    (net (code "82") (name "Net-(L1B-1)") (class "Default")
      (node (ref "B1") (pin "AC2") (pinfunction "AC2_AC2") (pintype "passive"))
      (node (ref "C2") (pin "2") (pinfunction "2_2") (pintype "passive"))
      (node (ref "C5") (pin "2") (pinfunction "2_2") (pintype "passive"))
      (node (ref "L1") (pin "3") (pinfunction "1_3") (pintype "passive"))
      (node (ref "SAR2") (pin "2") (pinfunction "P$2_2") (pintype "bidirectional"))
    )
    (net (code "83") (name "Net-(L1B-2)") (class "Default")
      (node (ref "C1") (pin "2") (pinfunction "2_2") (pintype "passive"))
      (node (ref "C5A") (pin "2") (pinfunction "2_2") (pintype "passive"))
      (node (ref "L1") (pin "4") (pinfunction "2_4") (pintype "passive"))
      (node (ref "R3") (pin "2") (pinfunction "2_2") (pintype "passive"))
      (node (ref "SAR2") (pin "1") (pinfunction "P$1_1") (pintype "bidirectional"))
      (node (ref "X2") (pin "3") (pinfunction "1_3") (pintype "passive"))
    )
    (net (code "84") (name "Net-(LED1-PadC)") (class "Default")
      (node (ref "LED1") (pin "C") (pinfunction "C_C") (pintype "passive"))
      (node (ref "R14") (pin "1") (pinfunction "1_1") (pintype "passive"))
    )
    (net (code "85") (name "Net-(OK1-A)") (class "Default")
      (node (ref "OK1") (pin "1") (pinfunction "A_1") (pintype "passive"))
      (node (ref "R18") (pin "2") (pinfunction "2_2") (pintype "passive"))
    )
    (net (code "86") (name "Net-(OK1-C)") (class "Default")
      (node (ref "OK1") (pin "2") (pinfunction "C_2") (pintype "passive"))
      (node (ref "R22") (pin "1") (pinfunction "1_1") (pintype "passive"))
      (node (ref "ZD3") (pin "C") (pinfunction "C_C") (pintype "passive"))
    )
    (net (code "87") (name "Net-(OK2-A)") (class "Default")
      (node (ref "OK2") (pin "1") (pinfunction "A_1") (pintype "passive"))
      (node (ref "R70") (pin "1") (pinfunction "1_1") (pintype "passive"))
      (node (ref "R78") (pin "1") (pinfunction "1_1") (pintype "passive"))
    )
    (net (code "88") (name "Net-(Q1-B)") (class "Default")
      (node (ref "C8") (pin "1") (pinfunction "1_1") (pintype "passive"))
      (node (ref "Q1") (pin "1") (pinfunction "B_1") (pintype "passive"))
      (node (ref "R5") (pin "2") (pinfunction "2_2") (pintype "passive"))
      (node (ref "ZD2") (pin "C") (pinfunction "C_C") (pintype "passive"))
    )
    (net (code "89") (name "Net-(Q6-PadB)") (class "Default")
      (node (ref "Q6") (pin "B") (pinfunction "B_B") (pintype "passive"))
      (node (ref "R50") (pin "2") (pinfunction "2_2") (pintype "passive"))
      (node (ref "R52") (pin "1") (pinfunction "1_1") (pintype "passive"))
    )
    (net (code "90") (name "Net-(R1-Pad2)") (class "Default")
      (node (ref "R1") (pin "2") (pinfunction "2_2") (pintype "passive"))
      (node (ref "R3") (pin "1") (pinfunction "1_1") (pintype "passive"))
    )
    (net (code "91") (name "Net-(R8-Pad2)") (class "Default")
      (node (ref "R8") (pin "2") (pinfunction "2_2") (pintype "passive"))
      (node (ref "R9") (pin "1") (pinfunction "1_1") (pintype "passive"))
    )
    (net (code "92") (name "Net-(R29-Pad1)") (class "Default")
      (node (ref "R29") (pin "1") (pinfunction "1_1") (pintype "passive"))
      (node (ref "R31") (pin "2") (pinfunction "2_2") (pintype "passive"))
    )
    (net (code "93") (name "Net-(R38-Pad2)") (class "Default")
      (node (ref "R38") (pin "2") (pinfunction "2_2") (pintype "passive"))
      (node (ref "R42") (pin "1") (pinfunction "1_1") (pintype "passive"))
    )
    (net (code "94") (name "Net-(R65-Pad1)") (class "Default")
      (node (ref "R65") (pin "1") (pinfunction "1_1") (pintype "passive"))
      (node (ref "R71") (pin "2") (pinfunction "2_2") (pintype "passive"))
    )
    (net (code "95") (name "Net-(R67-Pad2)") (class "Default")
      (node (ref "R67") (pin "2") (pinfunction "2_2") (pintype "passive"))
      (node (ref "R68") (pin "1") (pinfunction "1_1") (pintype "passive"))
    )
    (net (code "96") (name "Net-(SAR1-P$1)") (class "Default")
      (node (ref "C1") (pin "1") (pinfunction "1_1") (pintype "passive"))
      (node (ref "C6A") (pin "2") (pinfunction "2_2") (pintype "passive"))
      (node (ref "L1") (pin "2") (pinfunction "2_2") (pintype "passive"))
      (node (ref "R1") (pin "1") (pinfunction "1_1") (pintype "passive"))
      (node (ref "SAR1") (pin "1") (pinfunction "P$1_1") (pintype "bidirectional"))
      (node (ref "X2") (pin "2") (pinfunction "1_2") (pintype "passive"))
    )
    (net (code "97") (name "Net-(SAR1-P$2)") (class "Default")
      (node (ref "B1") (pin "AC1") (pinfunction "AC1_AC1") (pintype "passive"))
      (node (ref "C2") (pin "1") (pinfunction "1_1") (pintype "passive"))
      (node (ref "C6") (pin "2") (pinfunction "2_2") (pintype "passive"))
      (node (ref "L1") (pin "1") (pinfunction "1_1") (pintype "passive"))
      (node (ref "SAR1") (pin "2") (pinfunction "P$2_2") (pintype "bidirectional"))
    )
    (net (code "98") (name "Net-(TP5-P$1)") (class "Default")
      (node (ref "C42") (pin "1") (pinfunction "1_1") (pintype "passive"))
      (node (ref "R42") (pin "2") (pinfunction "2_2") (pintype "passive"))
      (node (ref "R44") (pin "2") (pinfunction "2_2") (pintype "passive"))
      (node (ref "R45") (pin "1") (pinfunction "1_1") (pintype "passive"))
      (node (ref "TP5") (pin "1") (pinfunction "P$1_1") (pintype "bidirectional"))
    )
    (net (code "99") (name "Net-(TR1-P2_DOT)") (class "Default")
      (node (ref "D4") (pin "A") (pinfunction "A_A") (pintype "passive"))
      (node (ref "IC3") (pin "13") (pinfunction "DRAIN_13") (pintype "output"))
      (node (ref "IC3") (pin "14") (pinfunction "DRAIN_14") (pintype "output"))
      (node (ref "IC3") (pin "15") (pinfunction "DRAIN_15") (pintype "output"))
      (node (ref "IC3") (pin "16") (pinfunction "DRAIN_16") (pintype "output"))
      (node (ref "TR1") (pin "4") (pinfunction "P2_DOT_4") (pintype "passive"))
    )
    (net (code "100") (name "Net-(TR1-S2)") (class "Default")
      (node (ref "C18") (pin "2") (pinfunction "2_2") (pintype "passive"))
      (node (ref "D5") (pin "C") (pinfunction "C_C") (pintype "passive"))
      (node (ref "TR1") (pin "8") (pinfunction "S2_8") (pintype "passive"))
    )
    (net (code "101") (name "Net-(TR1-S3_DOT)") (class "Default")
      (node (ref "C9") (pin "2") (pinfunction "2_2") (pintype "passive"))
      (node (ref "D2") (pin "A") (pinfunction "A_A") (pintype "passive"))
      (node (ref "TR1") (pin "15") (pinfunction "S3_DOT_15") (pintype "passive"))
    )
    (net (code "102") (name "Net-(TR2-P_DOT)") (class "Default")
      (node (ref "Q2") (pin "D") (pinfunction "D_D") (pintype "passive"))
      (node (ref "TR2") (pin "8") (pinfunction "P_DOT_8") (pintype "passive"))
    )
    (net (code "103") (name "Net-(TR2-S)") (class "Default")
      (node (ref "D12") (pin "A") (pinfunction "A_A") (pintype "passive"))
      (node (ref "R23") (pin "1") (pinfunction "1_1") (pintype "passive"))
      (node (ref "TR2") (pin "3") (pinfunction "S_3") (pintype "passive"))
    )
    (net (code "104") (name "Net-(X3H-S)") (class "Default")
      (node (ref "C15") (pin "2") (pinfunction "2_2") (pintype "passive"))
      (node (ref "C16") (pin "2") (pinfunction "2_2") (pintype "passive"))
      (node (ref "D6") (pin "A") (pinfunction "A_A") (pintype "passive"))
      (node (ref "IC1") (pin "2") (pinfunction "IN_2") (pintype "input"))
      (node (ref "IC1") (pin "3") (pinfunction "IN_3") (pintype "input"))
      (node (ref "IC1") (pin "6") (pinfunction "IN_6") (pintype "input"))
      (node (ref "IC1") (pin "7") (pinfunction "IN_7") (pintype "input"))
      (node (ref "L3") (pin "2") (pinfunction "2_2") (pintype "passive"))
      (node (ref "X3") (pin "8") (pinfunction "S_8") (pintype "passive"))
    )
    (net (code "105") (name "PE") (class "Default")
      (node (ref "C5") (pin "1") (pinfunction "1_1") (pintype "passive"))
      (node (ref "C5A") (pin "1") (pinfunction "1_1") (pintype "passive"))
      (node (ref "C6") (pin "1") (pinfunction "1_1") (pintype "passive"))
      (node (ref "C6A") (pin "1") (pinfunction "1_1") (pintype "passive"))
      (node (ref "JP2") (pin "NO") (pinfunction "NO_NO") (pintype "passive"))
      (node (ref "X2") (pin "1") (pinfunction "1_1") (pintype "passive"))
    )
    (net (code "106") (name "POUT+") (class "Default")
      (node (ref "C52") (pin "+") (pinfunction "+_+") (pintype "passive"))
      (node (ref "C53") (pin "+") (pinfunction "+_+") (pintype "passive"))
      (node (ref "C54") (pin "+") (pinfunction "+_+") (pintype "passive"))
      (node (ref "C55") (pin "1") (pinfunction "1_1") (pintype "passive"))
      (node (ref "L7") (pin "1") (pinfunction "1_1") (pintype "passive"))
      (node (ref "R54") (pin "1") (pinfunction "1_1") (pintype "passive"))
      (node (ref "R65") (pin "2") (pinfunction "2_2") (pintype "passive"))
      (node (ref "SH2") (pin "P$2") (pinfunction "GND_B_P$2") (pintype "bidirectional"))
      (node (ref "SH3") (pin "P$1") (pinfunction "GND_A_P$1") (pintype "bidirectional"))
    )
    (net (code "107") (name "PREG_OUT+") (class "Default")
      (node (ref "C56") (pin "1") (pinfunction "1_1") (pintype "passive"))
      (node (ref "C57") (pin "1") (pinfunction "1_1") (pintype "passive"))
      (node (ref "C58") (pin "1") (pinfunction "1_1") (pintype "passive"))
      (node (ref "C59") (pin "1") (pinfunction "1_1") (pintype "passive"))
      (node (ref "JP1") (pin "NC") (pinfunction "NC_NC") (pintype "passive"))
      (node (ref "L7") (pin "2") (pinfunction "2_2") (pintype "passive"))
      (node (ref "R54") (pin "2") (pinfunction "2_2") (pintype "passive"))
      (node (ref "R55") (pin "2") (pinfunction "2_2") (pintype "passive"))
      (node (ref "TP7") (pin "TIP") (pinfunction "TIP_TIP") (pintype "bidirectional"))
      (node (ref "X3") (pin "2") (pinfunction "S_2") (pintype "passive"))
      (node (ref "X4") (pin "1") (pinfunction "1_1") (pintype "passive"))
      (node (ref "ZD6") (pin "C") (pinfunction "C_C") (pintype "passive"))
    )
    (net (code "108") (name "PULL") (class "Default")
      (node (ref "D21") (pin "A") (pinfunction "A_A") (pintype "passive"))
      (node (ref "IC5") (pin "9") (pinfunction "PULL_9") (pintype "output"))
      (node (ref "R47") (pin "2") (pinfunction "2_2") (pintype "passive"))
    )
    (net (code "109") (name "PUSH") (class "Default")
      (node (ref "D20") (pin "A") (pinfunction "A_A") (pintype "passive"))
      (node (ref "IC5") (pin "8") (pinfunction "PUSH_8") (pintype "output"))
      (node (ref "R46") (pin "2") (pinfunction "2_2") (pintype "passive"))
    )
    (net (code "110") (name "PWRGOOD") (class "Default")
      (node (ref "IC10") (pin "7") (pinfunction "C_7") (pintype "passive"))
      (node (ref "IC2") (pin "5") (pinfunction "~{ERROR}_5") (pintype "input"))
      (node (ref "R15") (pin "2") (pinfunction "2_2") (pintype "passive"))
      (node (ref "R81") (pin "1") (pinfunction "1_1") (pintype "passive"))
      (node (ref "X3") (pin "4") (pinfunction "S_4") (pintype "passive"))
    )
    (net (code "111") (name "REF") (class "Default")
      (node (ref "C37") (pin "2") (pinfunction "2_2") (pintype "passive"))
      (node (ref "IC4") (pin "3") (pinfunction "VDDI_3") (pintype "power_in"))
      (node (ref "IC4") (pin "8") (pinfunction "VDDI_8") (pintype "power_in"))
      (node (ref "R35") (pin "2") (pinfunction "2_2") (pintype "passive"))
      (node (ref "ZD4") (pin "C") (pinfunction "C_C") (pintype "passive"))
    )
    (net (code "112") (name "S1_DOT_OUT") (class "Default")
      (node (ref "IC6") (pin "4") (pinfunction "VD1_4") (pintype "passive"))
      (node (ref "Q7") (pin "3") (pinfunction "D_3") (pintype "passive"))
      (node (ref "R56") (pin "1") (pinfunction "1_1") (pintype "passive"))
      (node (ref "R57") (pin "1") (pinfunction "1_1") (pintype "passive"))
      (node (ref "TR3") (pin "S1_DOT") (pinfunction "S1_DOT_S1_DOT") (pintype "passive"))
    )
    (net (code "113") (name "S1_OUT") (class "Default")
      (node (ref "SH2") (pin "P$1") (pinfunction "GND_A_P$1") (pintype "bidirectional"))
      (node (ref "TR3") (pin "S1") (pinfunction "S1_S1") (pintype "passive"))
    )
    (net (code "114") (name "S2_DOT_OUT") (class "Default")
      (node (ref "SH3") (pin "P$2") (pinfunction "GND_B_P$2") (pintype "bidirectional"))
      (node (ref "TR3") (pin "S2_DOT") (pinfunction "S2_DOT_S2_DOT") (pintype "passive"))
    )
    (net (code "115") (name "S2_OUT") (class "Default")
      (node (ref "IC6") (pin "5") (pinfunction "VD2_5") (pintype "passive"))
      (node (ref "Q8") (pin "3") (pinfunction "D_3") (pintype "passive"))
      (node (ref "R62") (pin "1") (pinfunction "1_1") (pintype "passive"))
      (node (ref "R63") (pin "1") (pinfunction "1_1") (pintype "passive"))
      (node (ref "TR3") (pin "S2") (pinfunction "S2_S2") (pintype "passive"))
    )
    (net (code "116") (name "SR_OUT1") (class "Default")
      (node (ref "D22") (pin "A") (pinfunction "A_A") (pintype "passive"))
      (node (ref "Q7") (pin "1") (pinfunction "G_1") (pintype "passive"))
      (node (ref "R58") (pin "1") (pinfunction "1_1") (pintype "passive"))
    )
    (net (code "117") (name "SR_OUT2") (class "Default")
      (node (ref "D23") (pin "A") (pinfunction "A_A") (pintype "passive"))
      (node (ref "Q8") (pin "1") (pinfunction "G_1") (pintype "passive"))
      (node (ref "R61") (pin "1") (pinfunction "1_1") (pintype "passive"))
    )
    (net (code "118") (name "U_MON") (class "Default")
      (node (ref "JP4") (pin "NC") (pinfunction "NC_NC") (pintype "passive"))
      (node (ref "X3") (pin "1") (pinfunction "S_1") (pintype "passive"))
    )
    (net (code "119") (name "V+") (class "Default")
      (node (ref "C23") (pin "+") (pinfunction "+_+") (pintype "passive"))
      (node (ref "C64") (pin "1") (pinfunction "1_1") (pintype "passive"))
      (node (ref "C67") (pin "1") (pinfunction "1_1") (pintype "passive"))
      (node (ref "C75") (pin "1") (pinfunction "1_1") (pintype "passive"))
      (node (ref "D7") (pin "A") (pinfunction "A_A") (pintype "passive"))
      (node (ref "D9") (pin "C") (pinfunction "C_C") (pintype "passive"))
      (node (ref "IC10") (pin "8") (pinfunction "V+_8") (pintype "power_in"))
      (node (ref "IC2") (pin "1") (pinfunction "OUT_1") (pintype "output"))
      (node (ref "IC7") (pin "8") (pinfunction "V+_8") (pintype "power_in"))
      (node (ref "IC8") (pin "8") (pinfunction "VCC+_8") (pintype "power_in"))
      (node (ref "R12") (pin "1") (pinfunction "1_1") (pintype "passive"))
      (node (ref "R15") (pin "1") (pinfunction "1_1") (pintype "passive"))
      (node (ref "R70") (pin "2") (pinfunction "2_2") (pintype "passive"))
      (node (ref "R72") (pin "2") (pinfunction "2_2") (pintype "passive"))
      (node (ref "X3") (pin "5") (pinfunction "S_5") (pintype "passive"))
    )
    (net (code "120") (name "V-") (class "Default")
      (node (ref "C17") (pin "2") (pinfunction "2_2") (pintype "passive"))
      (node (ref "C66") (pin "1") (pinfunction "1_1") (pintype "passive"))
      (node (ref "D3") (pin "A") (pinfunction "A_A") (pintype "passive"))
      (node (ref "D6") (pin "C") (pinfunction "C_C") (pintype "passive"))
      (node (ref "IC1") (pin "1") (pinfunction "OUT_1") (pintype "passive"))
      (node (ref "IC7") (pin "4") (pinfunction "V-_4") (pintype "power_in"))
      (node (ref "X3") (pin "7") (pinfunction "S_7") (pintype "passive"))
    )
    (net (code "121") (name "unconnected-(IC2-SD-Pad3)") (class "Default")
      (node (ref "IC2") (pin "3") (pinfunction "SD_3") (pintype "input"))
    )
    (net (code "122") (name "unconnected-(IC2-SENSE-Pad2)") (class "Default")
      (node (ref "IC2") (pin "2") (pinfunction "SENSE_2") (pintype "input"))
    )
    (net (code "123") (name "unconnected-(IC2-VTAP-Pad6)") (class "Default")
      (node (ref "IC2") (pin "6") (pinfunction "VTAP_6") (pintype "input"))
    )
    (net (code "124") (name "unconnected-(IC10A-BALANCE-Pad5)") (class "Default")
      (node (ref "IC10") (pin "5") (pinfunction "BALANCE_5") (pintype "input"))
    )
    (net (code "125") (name "unconnected-(IC10A-BAL{slash}STRB-Pad6)") (class "Default")
      (node (ref "IC10") (pin "6") (pinfunction "BAL/STRB_6") (pintype "input"))
    )
  )
)
